# RFFI_pwrCtrl_Integrated_2021-05-07.net
KiCad netlist of a schematic drawn in EasyEDA
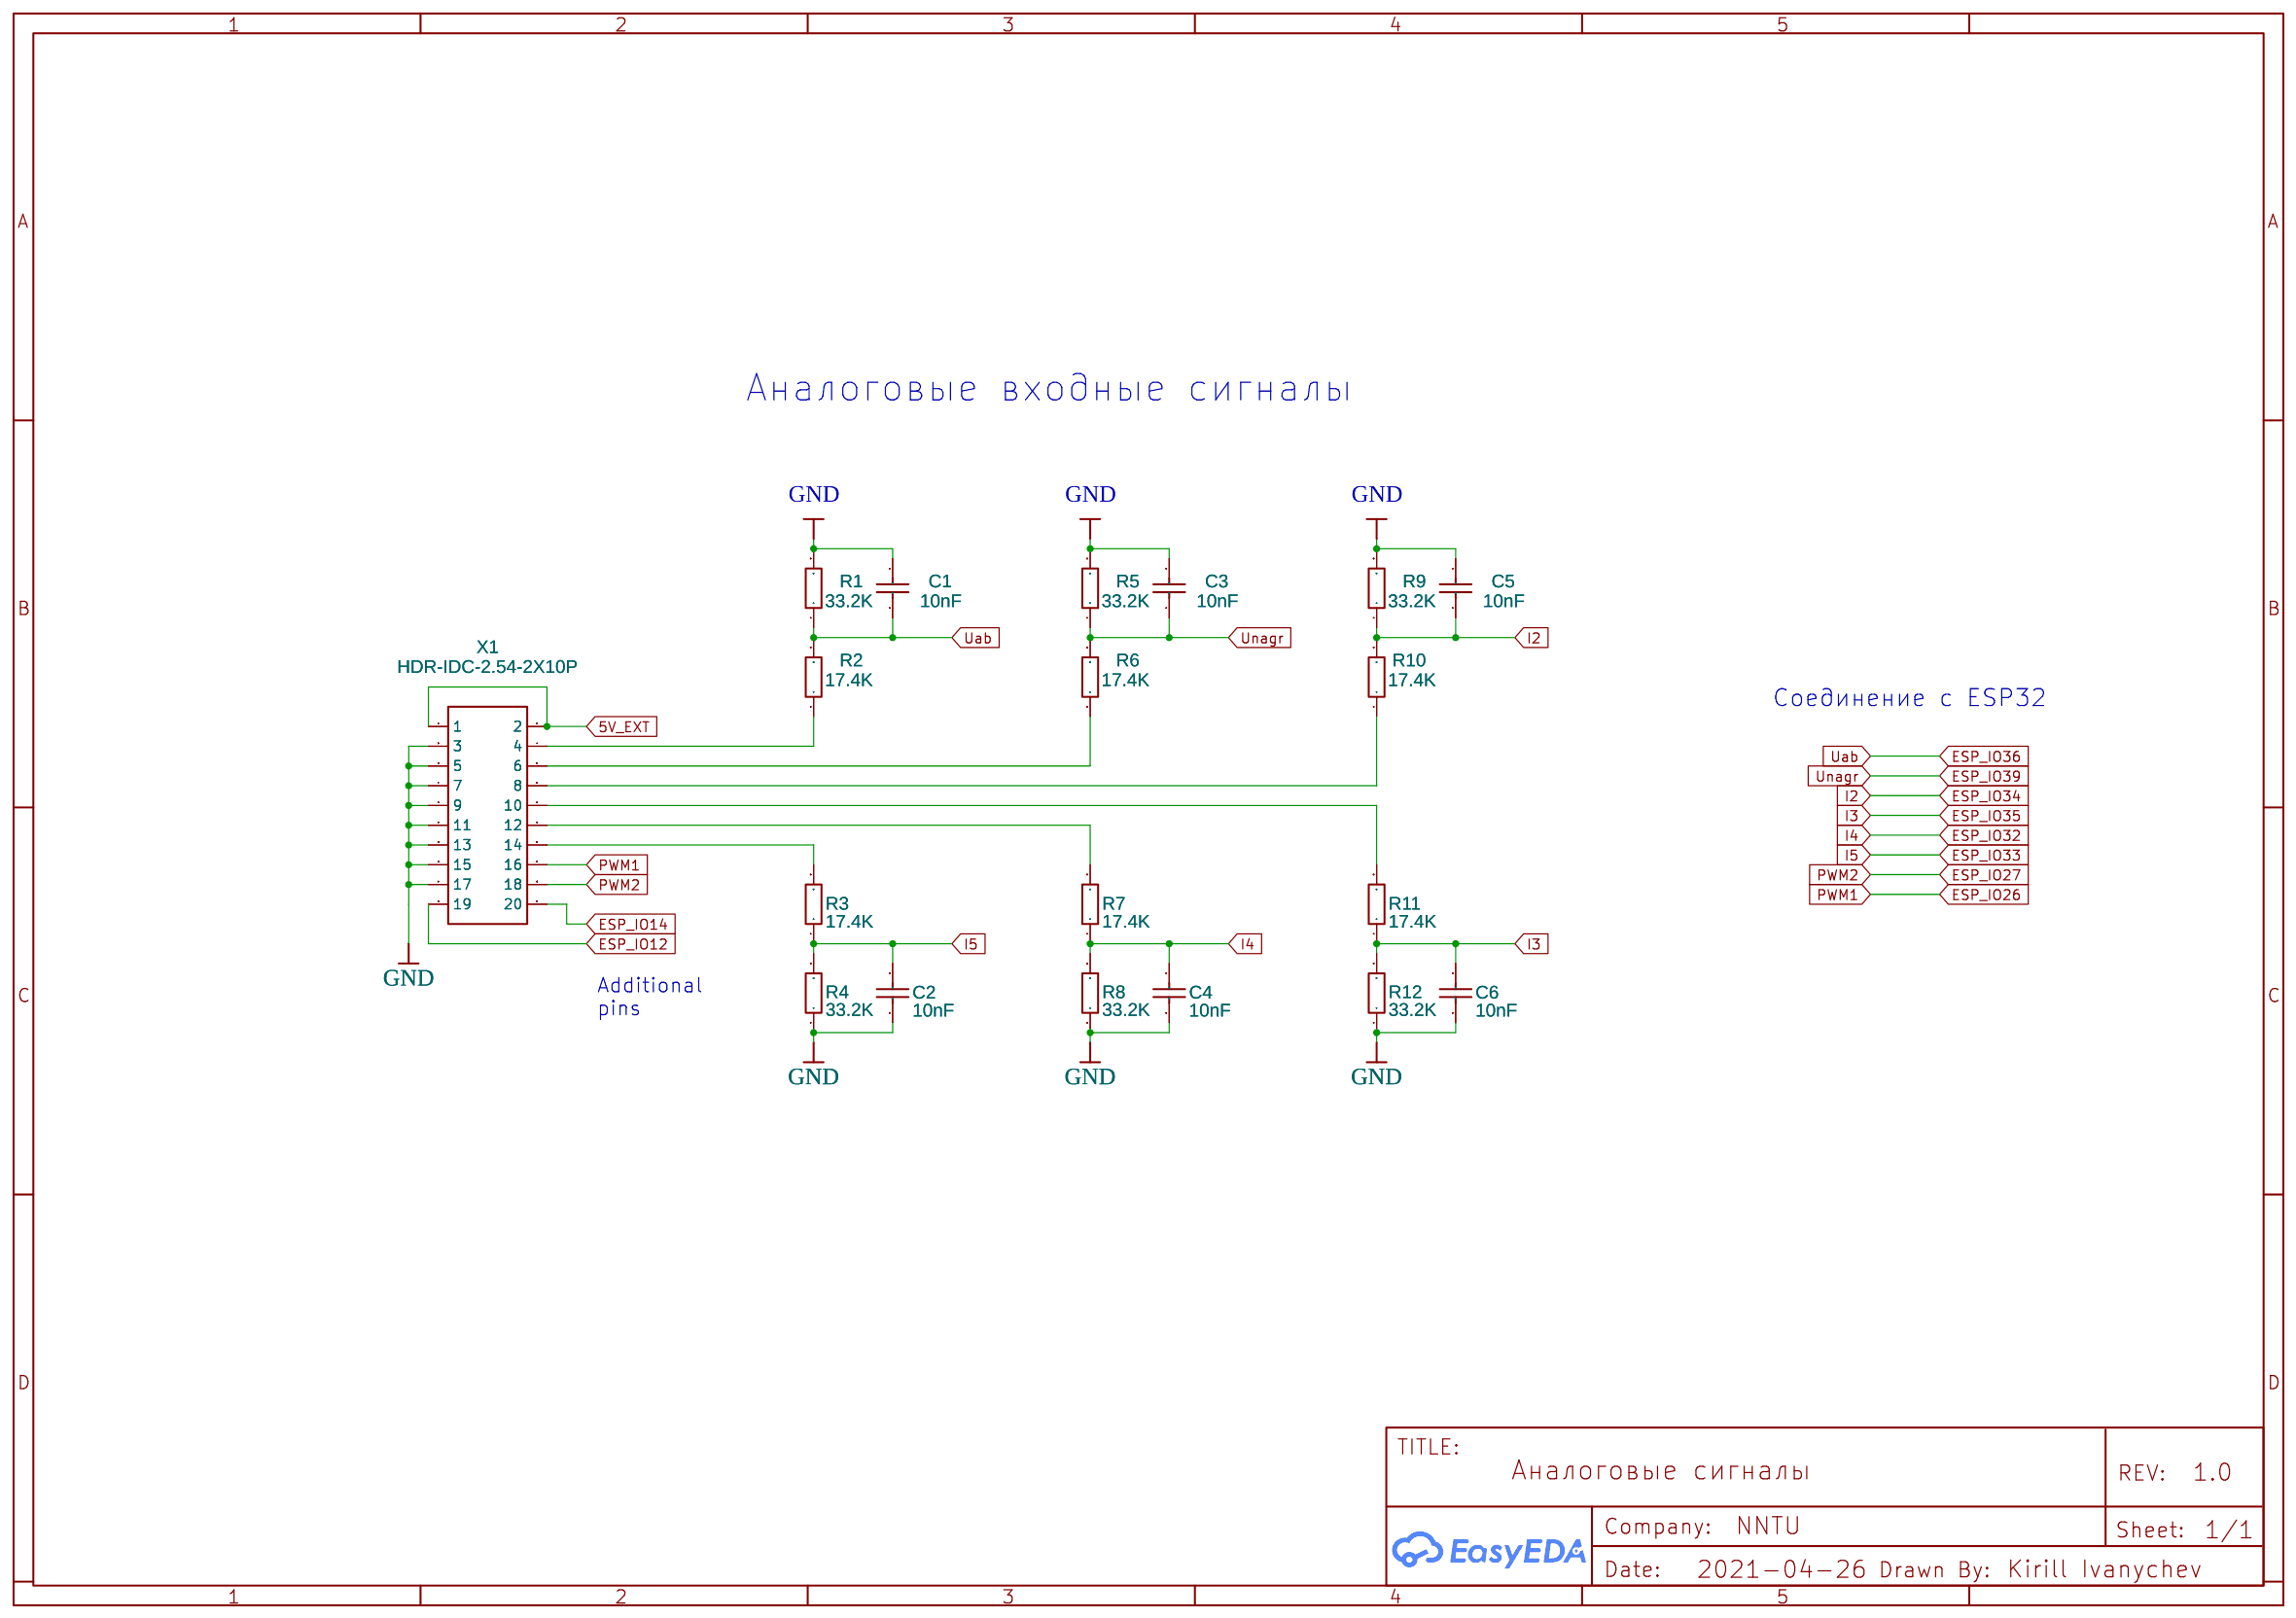
[diagram p0: Analog Signals]
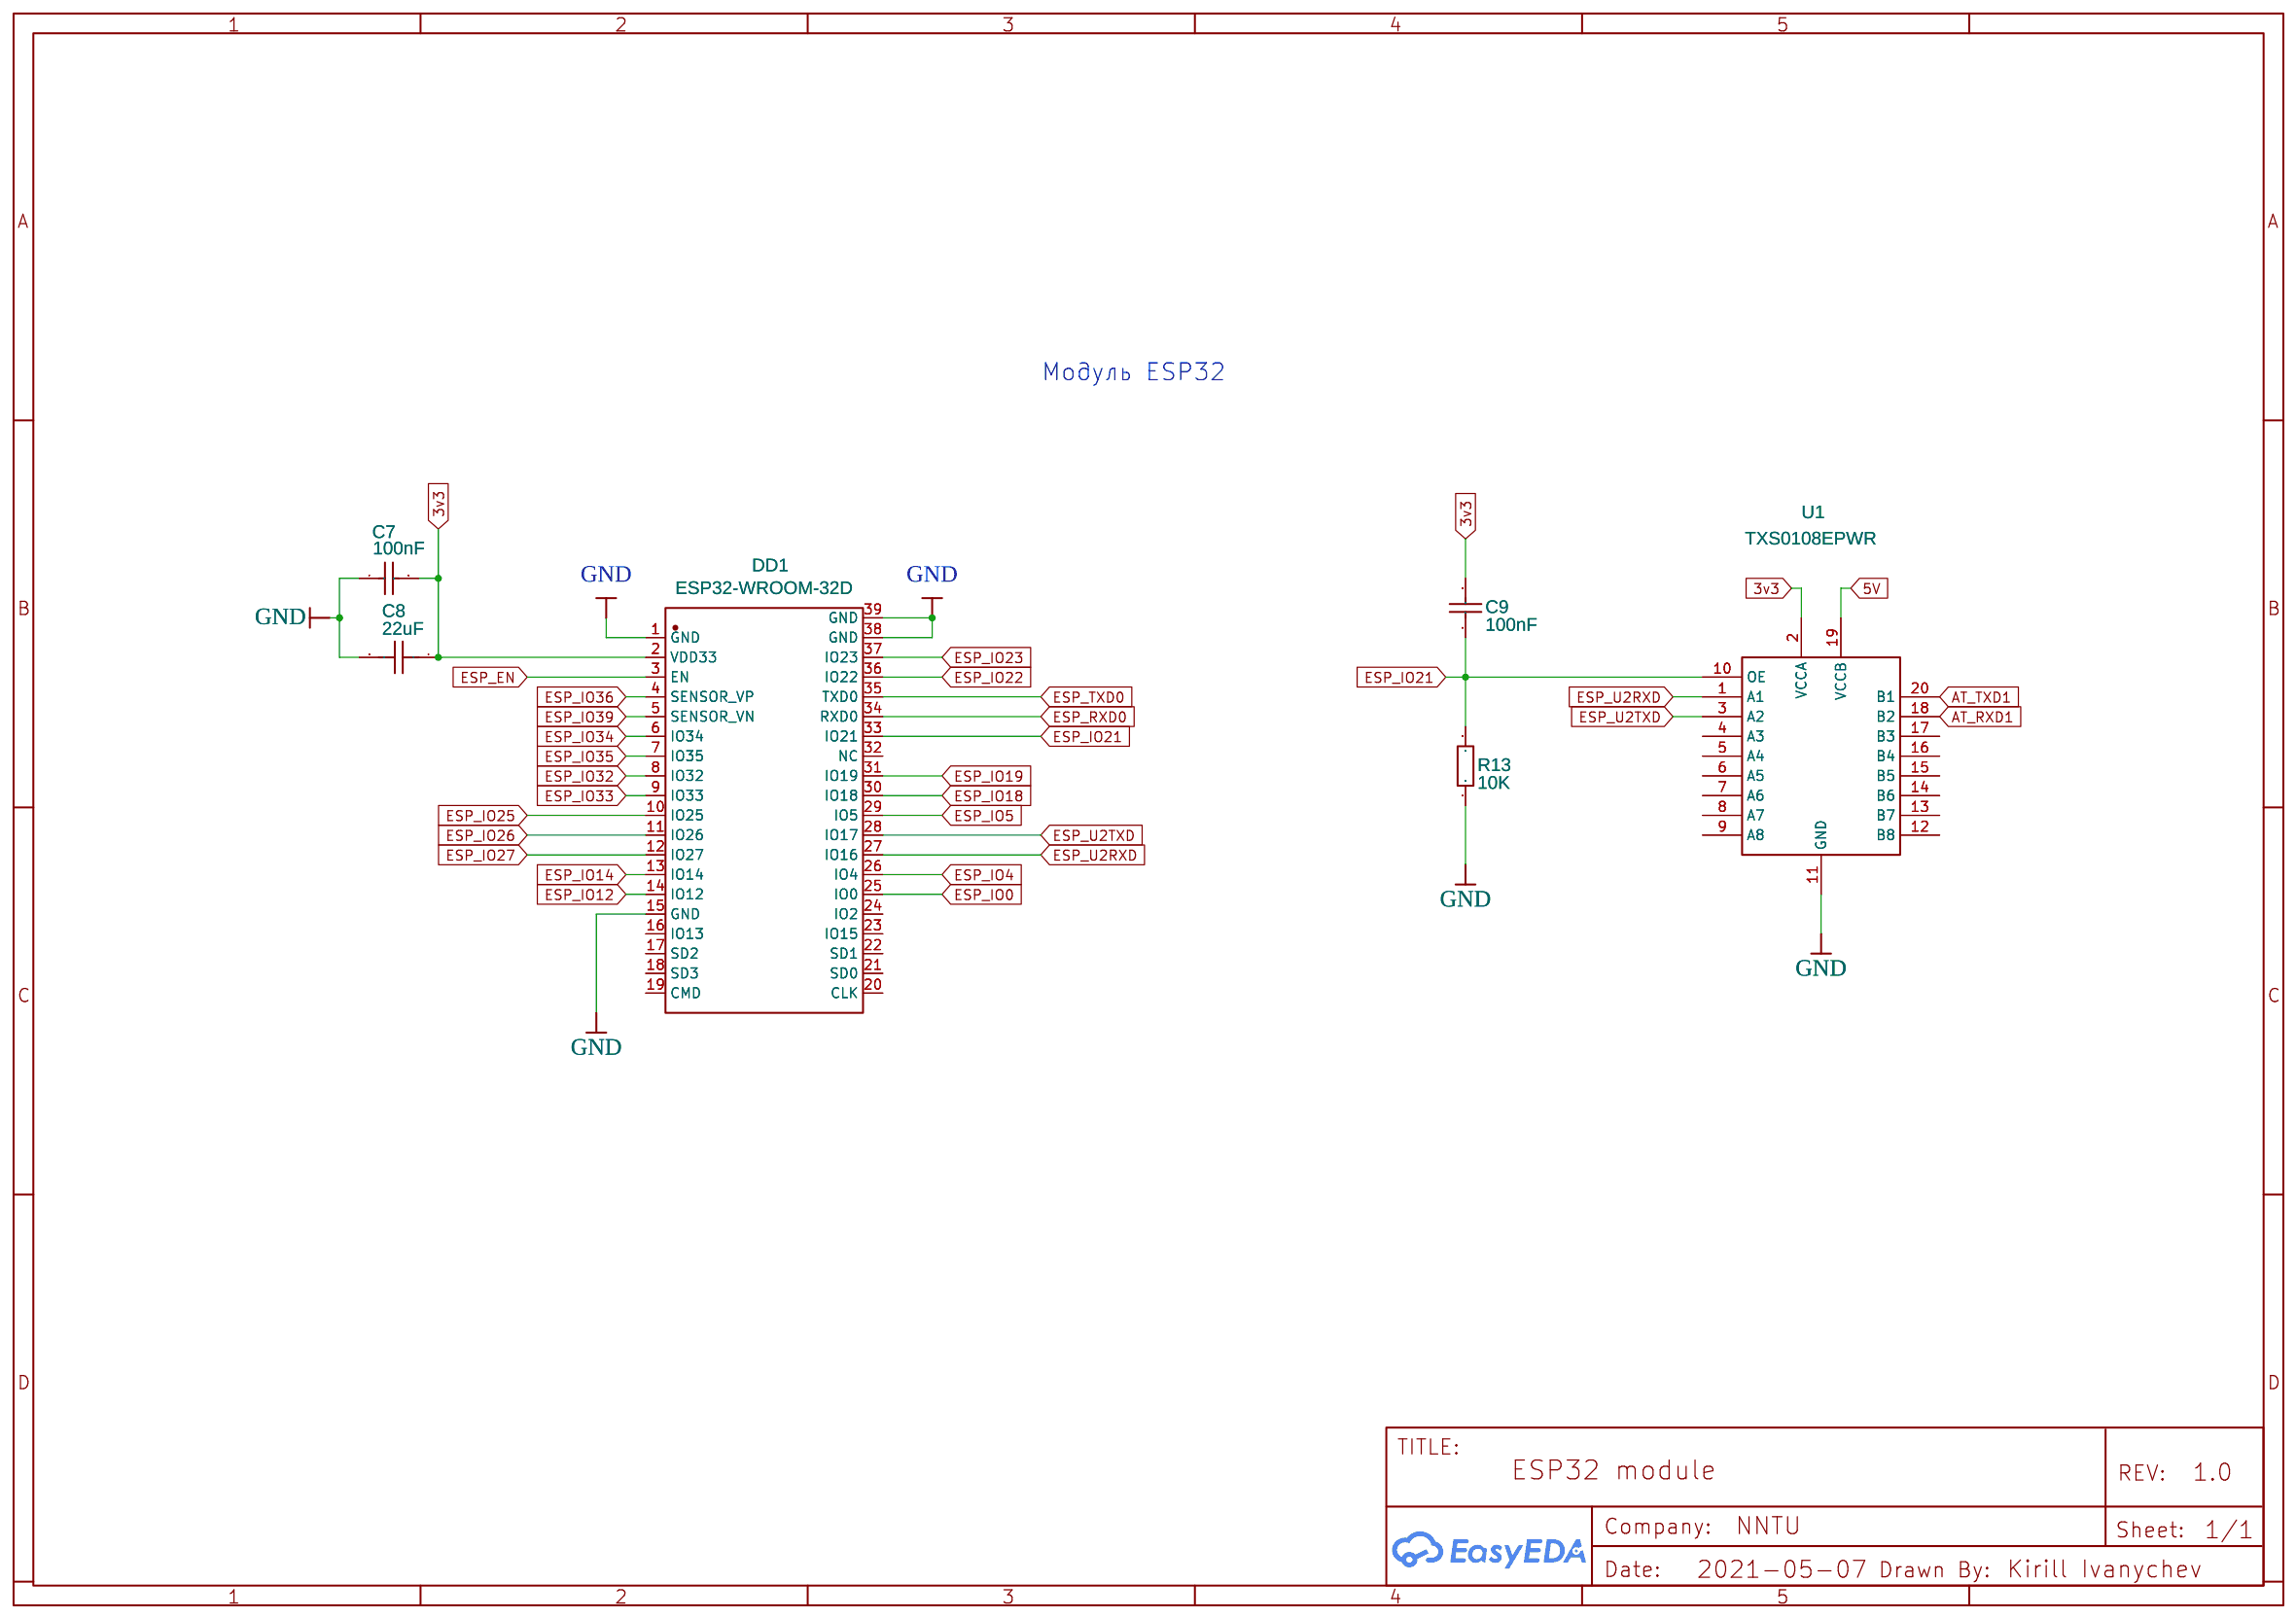
[diagram p1: ESP32 module]
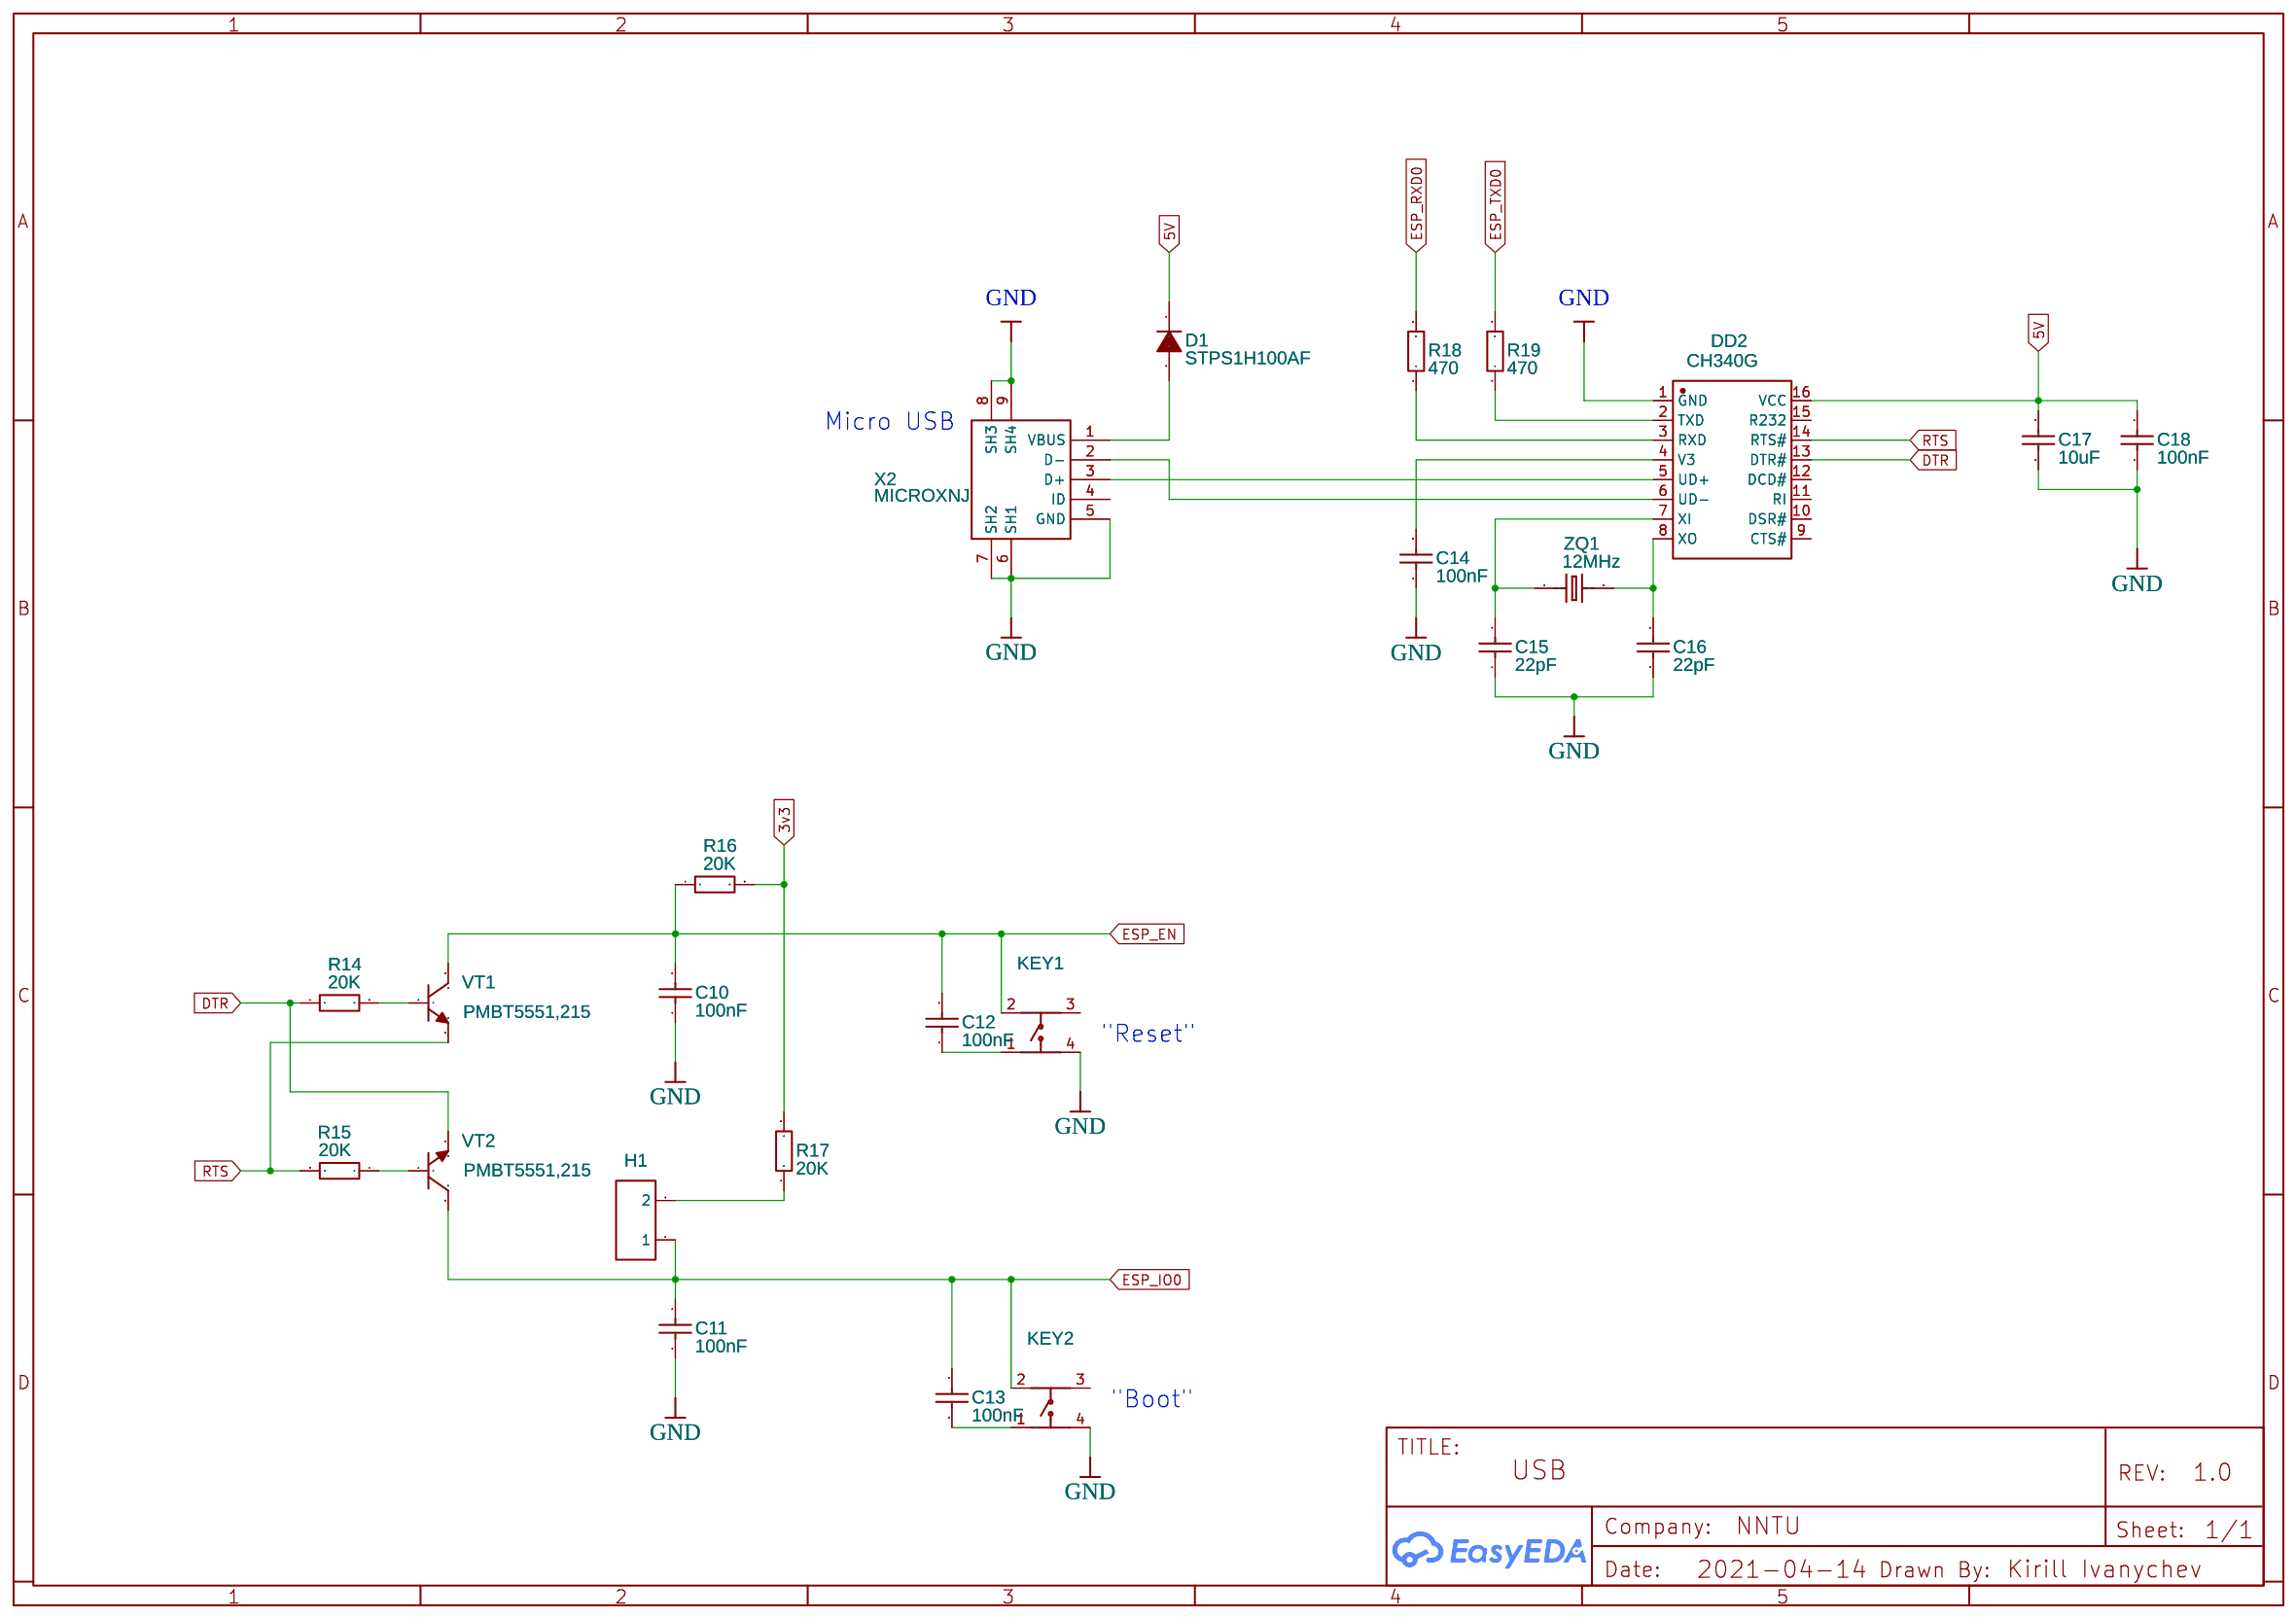
[diagram p2: USB]
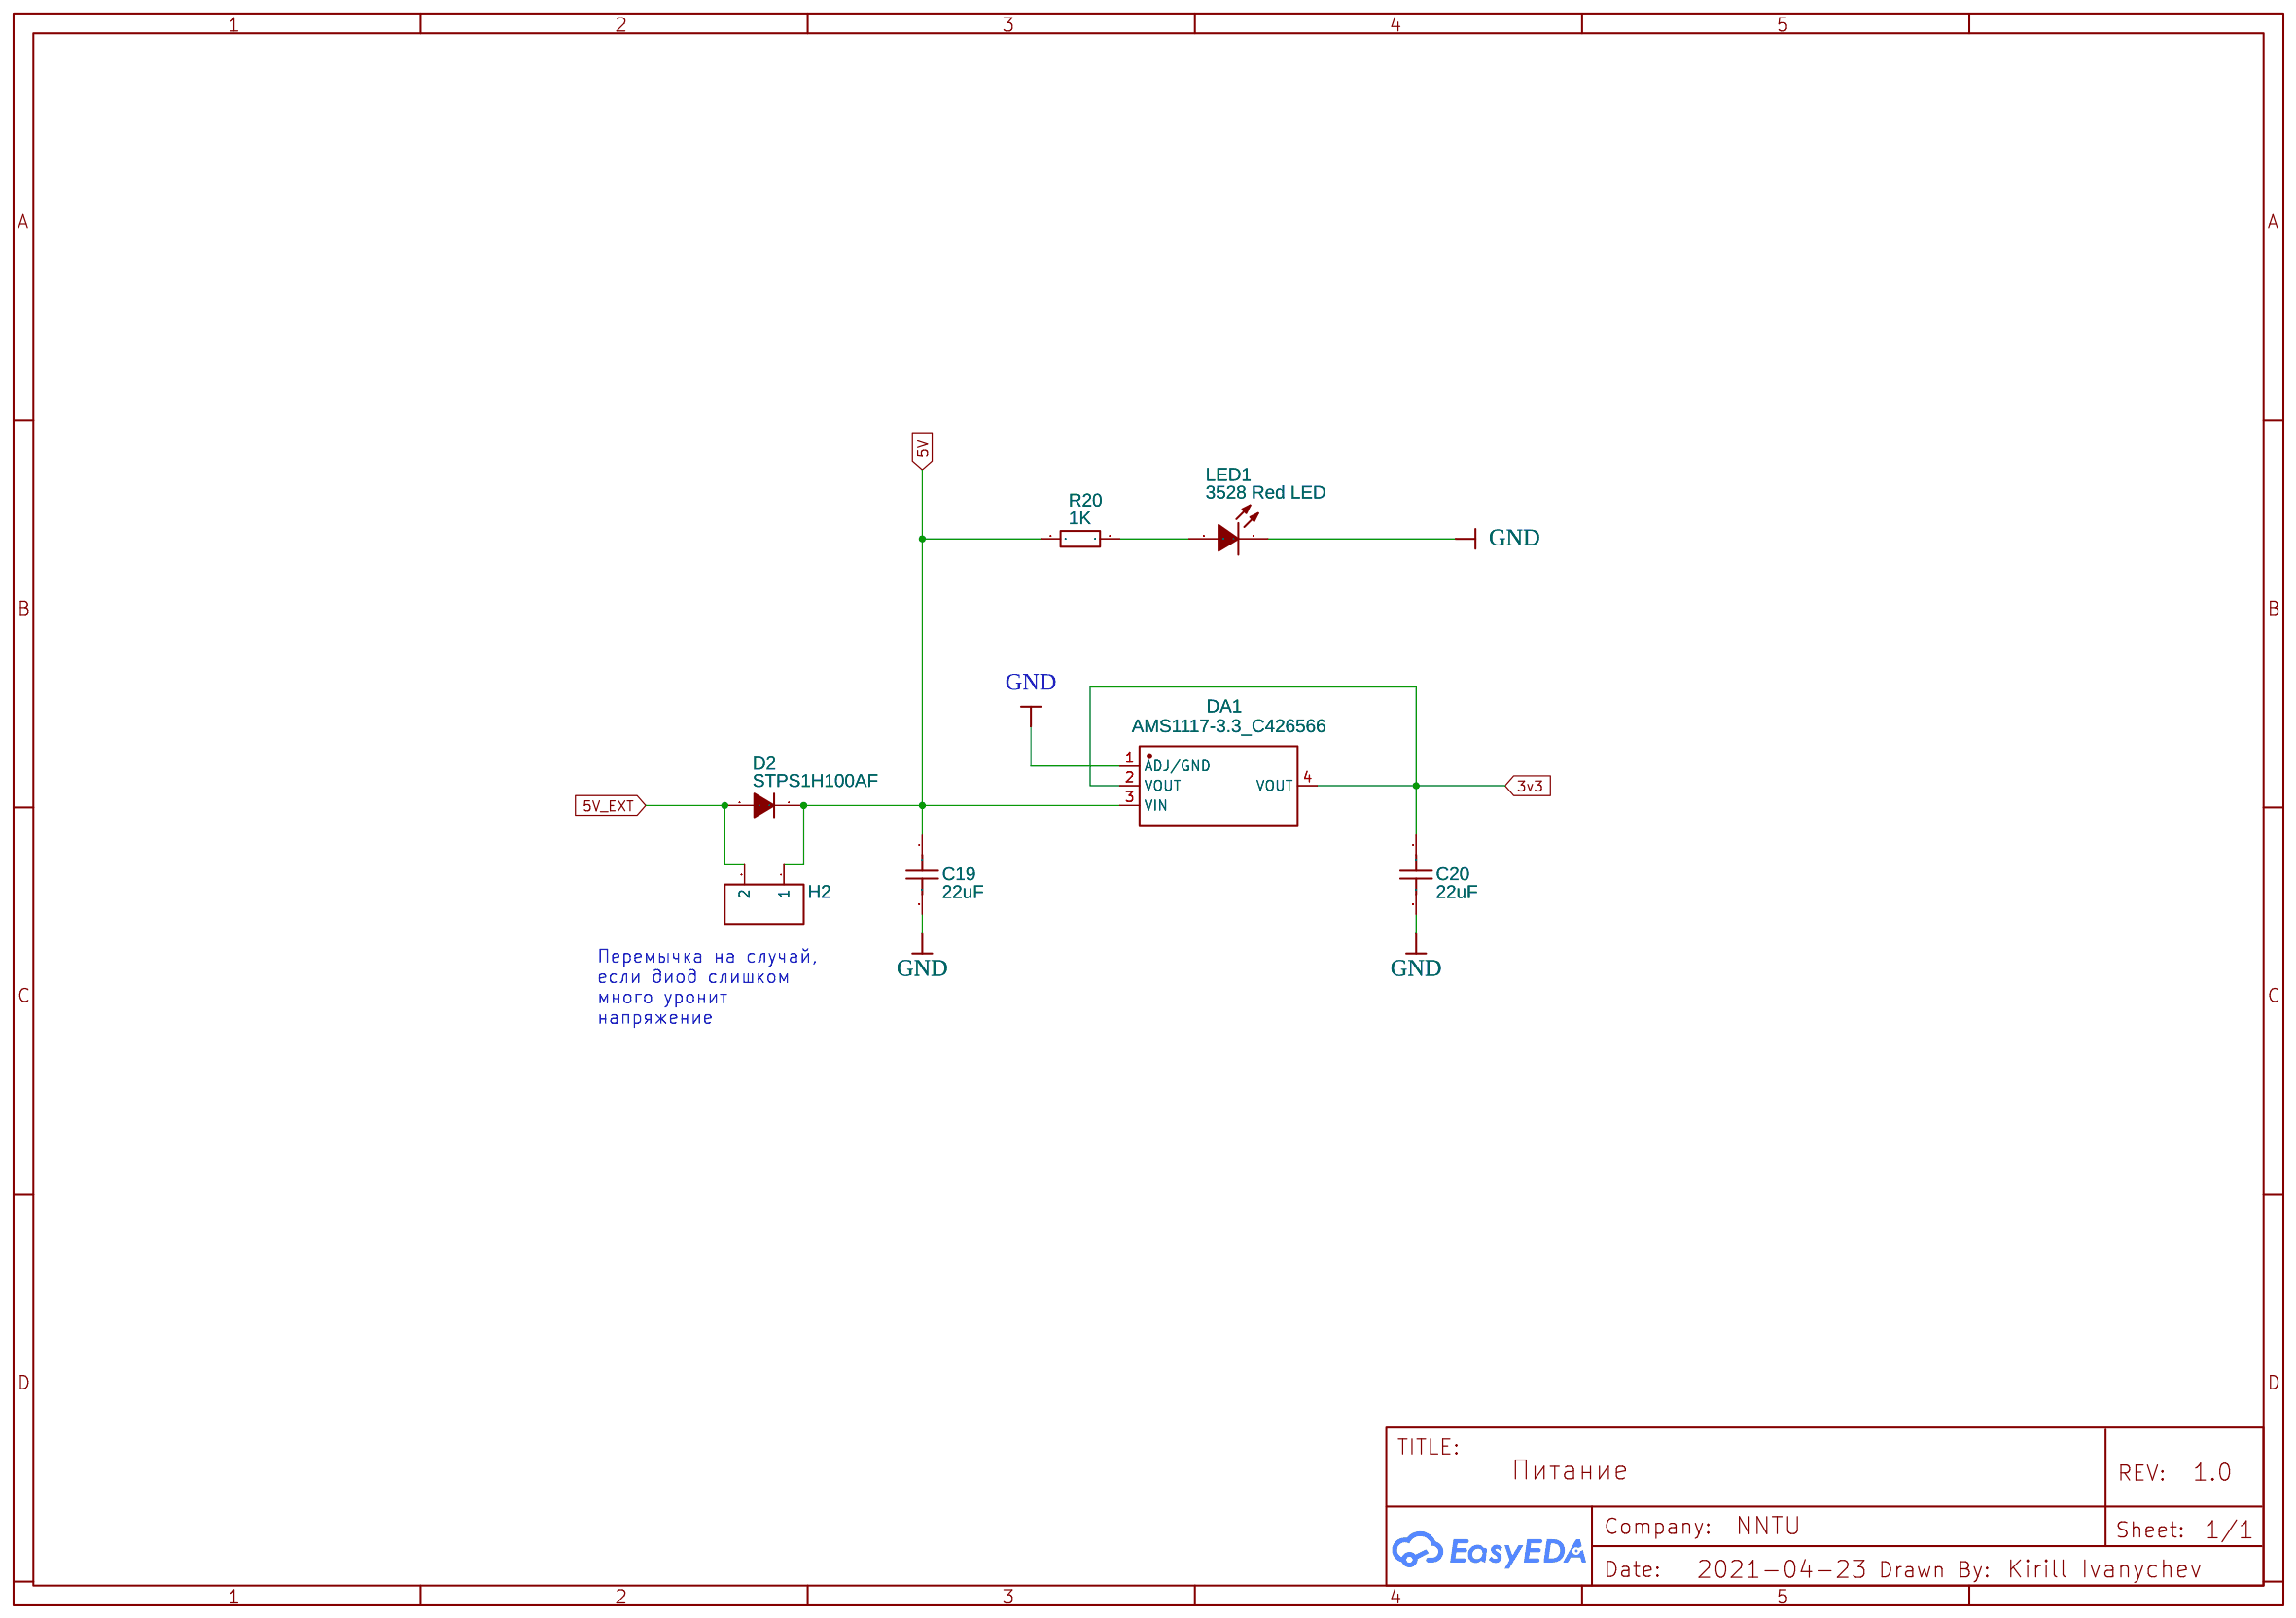
[diagram p3: Power]
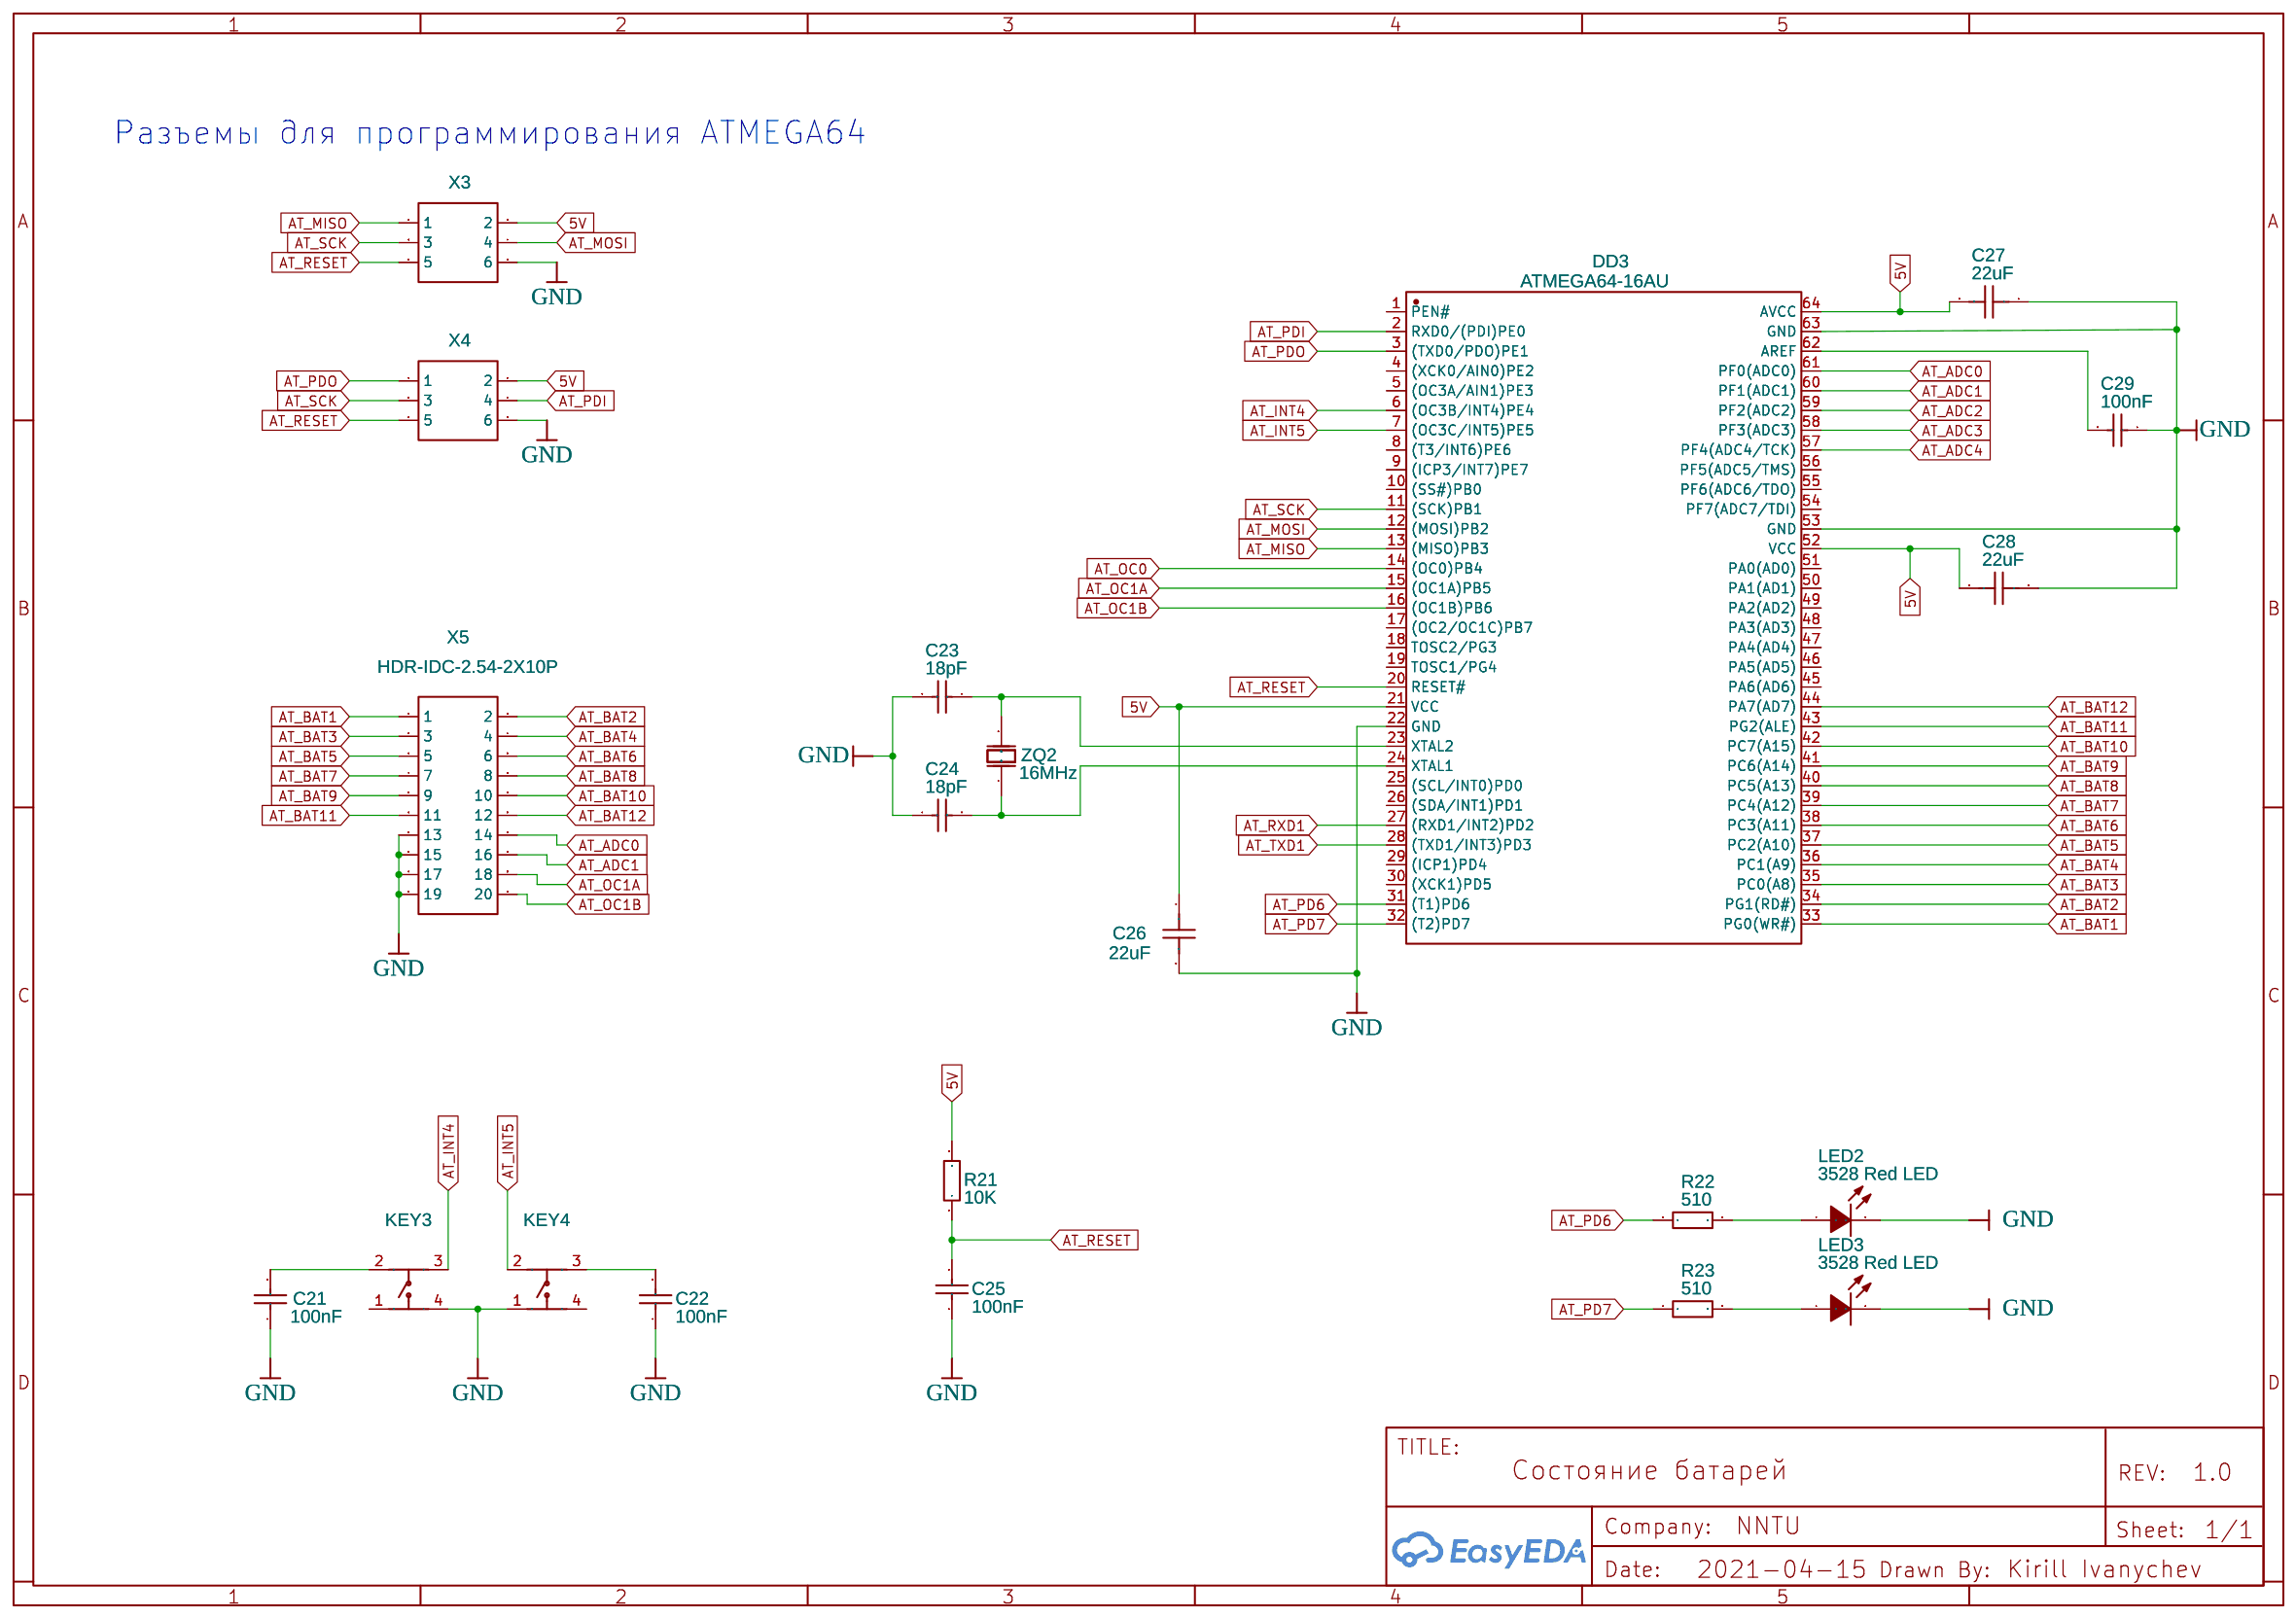
[diagram p4: Batteries]
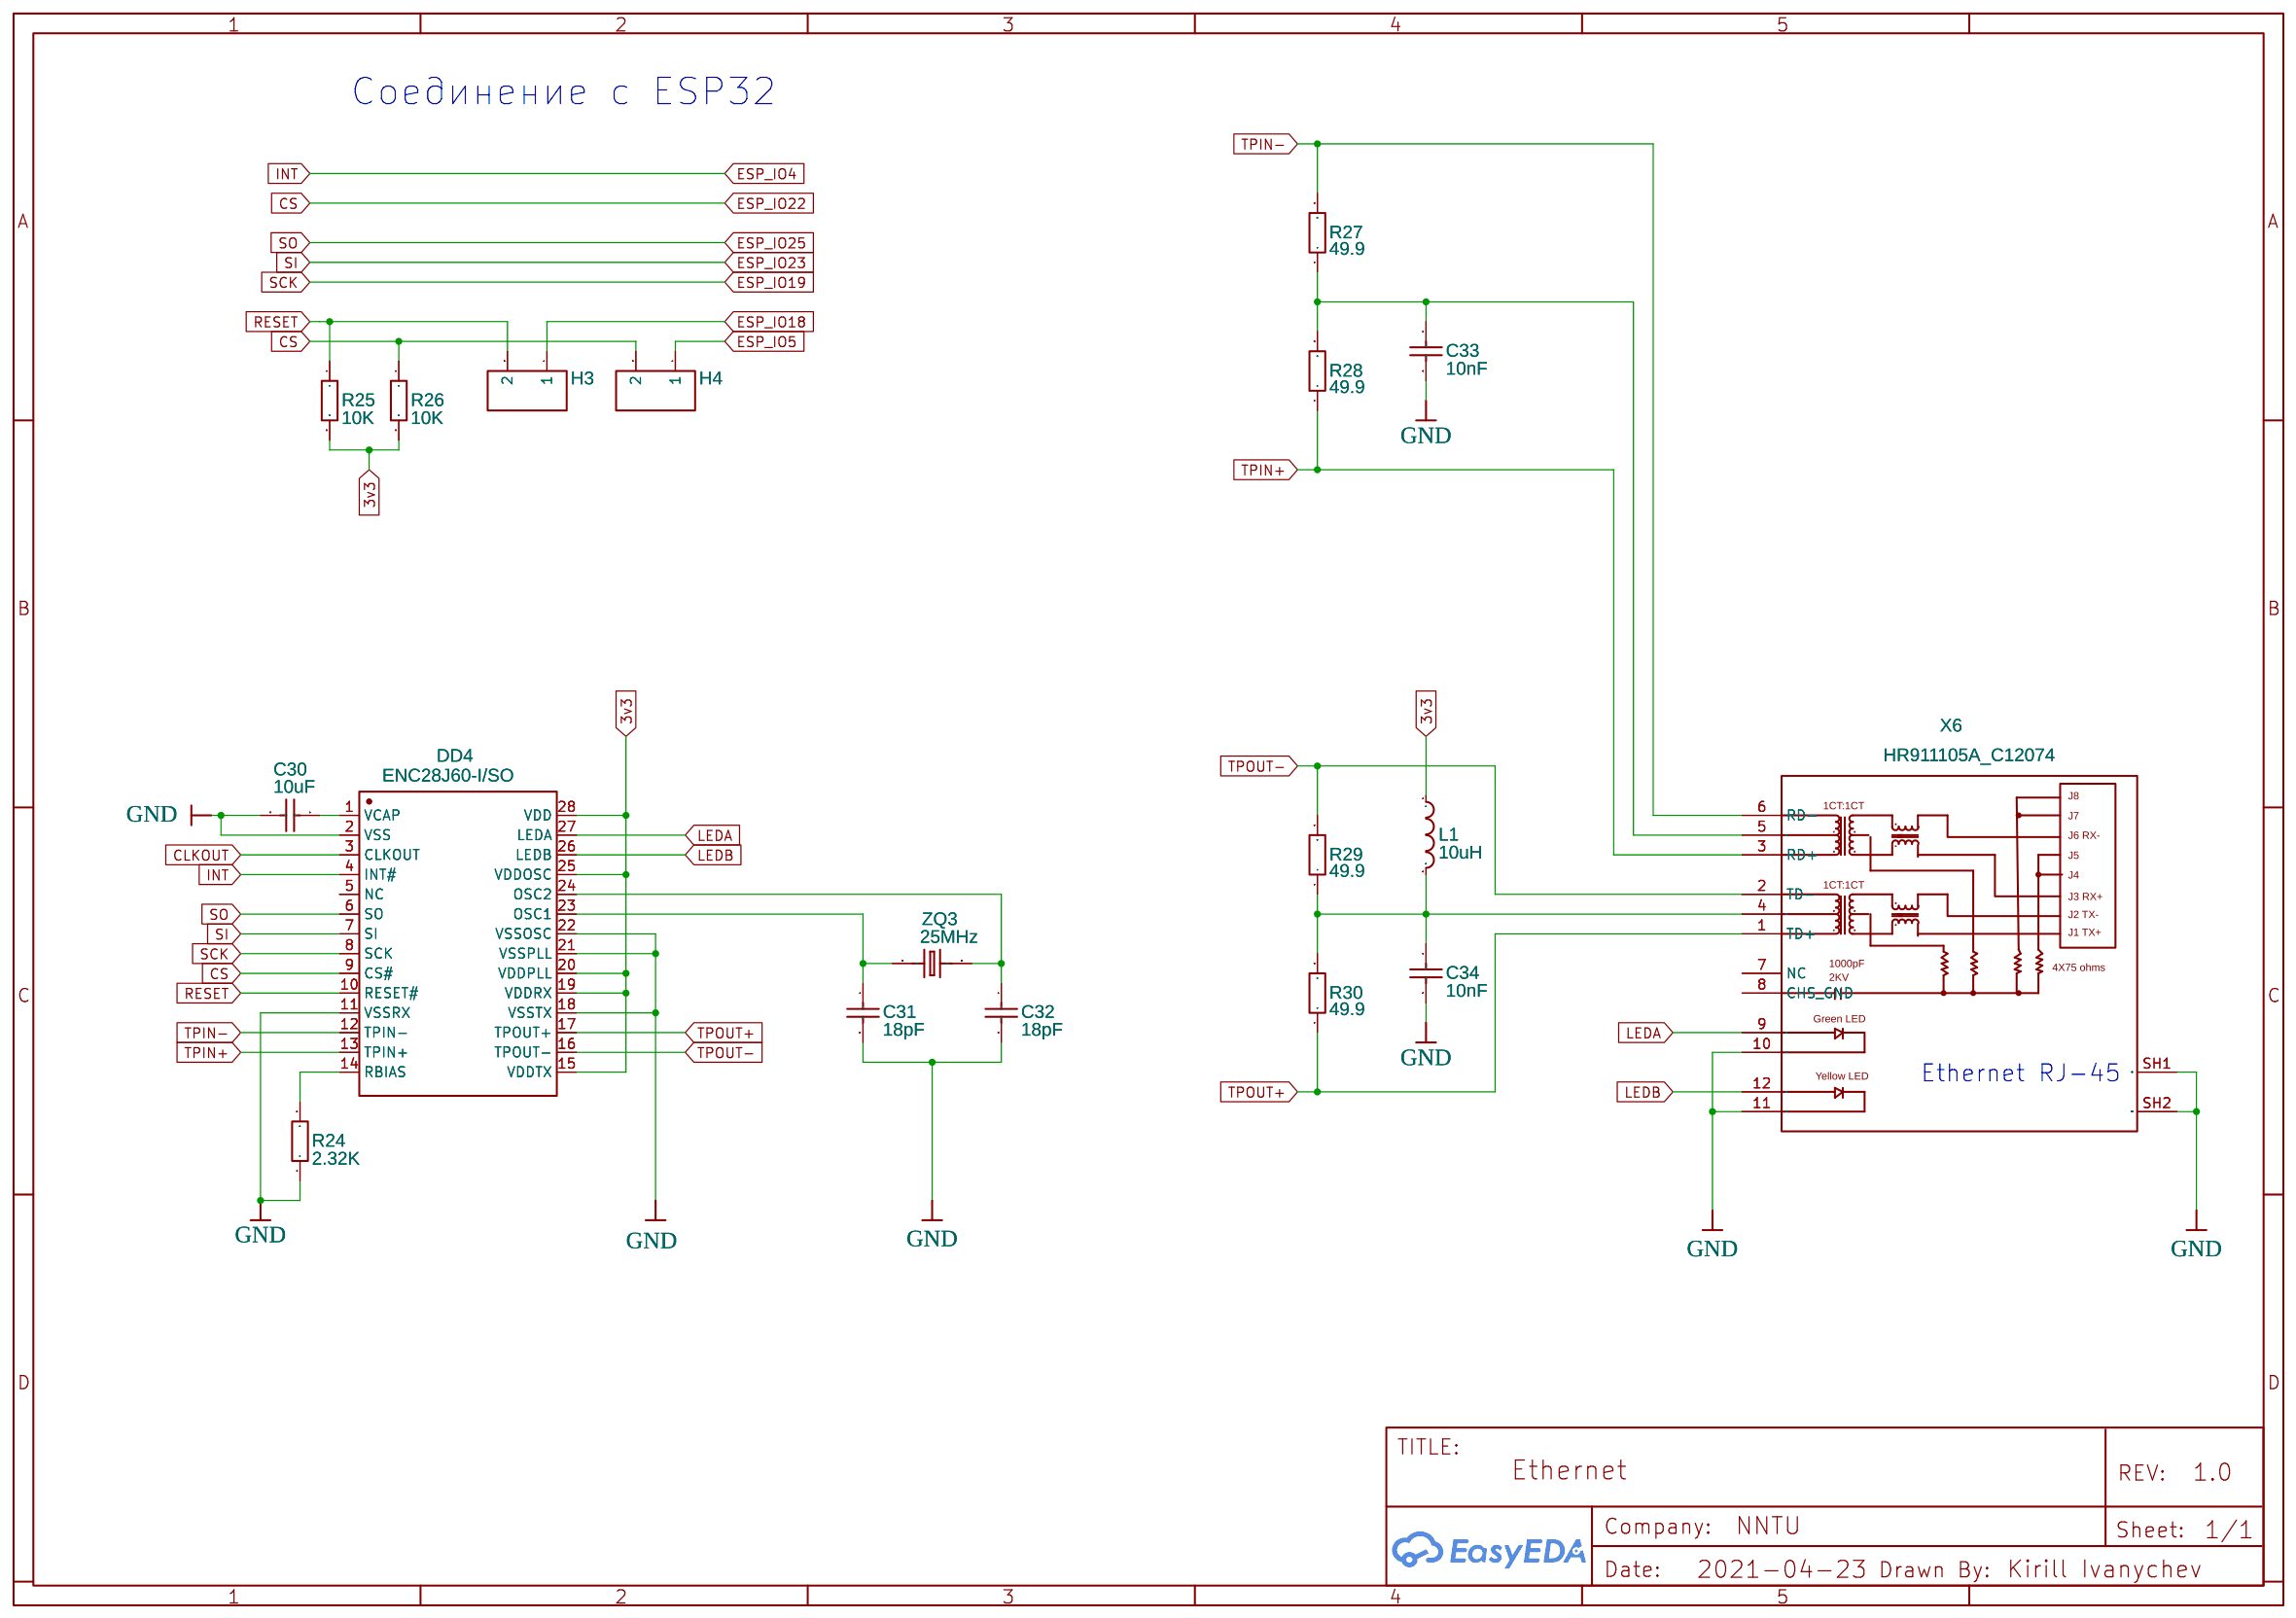
[diagram p5: Ethernet]

(export (version "E")
  (design (tool "Eeschema 10.0.6"))
  (components
    (comp (ref "C1")
      (value "10nF")
      (fields
        (field (name "BOM_Manufacturer Part") "1206B103K500NT")
        (field (name "BOM_Supplier Part") "C1846")
      )
      (libsource (lib "") (part "1206B103K500NT"))
    )
    (comp (ref "C2")
      (value "10nF")
      (fields
        (field (name "BOM_Manufacturer Part") "1206B103K500NT")
        (field (name "BOM_Supplier Part") "C1846")
      )
      (libsource (lib "") (part "1206B103K500NT_1"))
    )
    (comp (ref "C3")
      (value "10nF")
      (fields
        (field (name "BOM_Manufacturer Part") "1206B103K500NT")
        (field (name "BOM_Supplier Part") "C1846")
      )
      (libsource (lib "") (part "1206B103K500NT"))
    )
    (comp (ref "C4")
      (value "10nF")
      (fields
        (field (name "BOM_Manufacturer Part") "1206B103K500NT")
        (field (name "BOM_Supplier Part") "C1846")
      )
      (libsource (lib "") (part "1206B103K500NT_1"))
    )
    (comp (ref "C5")
      (value "10nF")
      (fields
        (field (name "BOM_Manufacturer Part") "1206B103K500NT")
        (field (name "BOM_Supplier Part") "C1846")
      )
      (libsource (lib "") (part "1206B103K500NT"))
    )
    (comp (ref "C6")
      (value "10nF")
      (fields
        (field (name "BOM_Manufacturer Part") "1206B103K500NT")
        (field (name "BOM_Supplier Part") "C1846")
      )
      (libsource (lib "") (part "1206B103K500NT_1"))
    )
    (comp (ref "R1")
      (value "33.2K")
      (fields
        (field (name "BOM_Manufacturer Part") "0603WAF3322T5E")
        (field (name "BOM_Supplier Part") "C23003")
      )
      (libsource (lib "") (part "0603WAF3322T5E"))
    )
    (comp (ref "R2")
      (value "17.4K")
      (fields
        (field (name "BOM_Manufacturer Part") "0402WGF1742TCE")
        (field (name "BOM_Supplier Part") "C26957")
      )
      (libsource (lib "") (part "0402WGF1742TCE"))
    )
    (comp (ref "R3")
      (value "17.4K")
      (fields
        (field (name "BOM_Manufacturer Part") "0402WGF1742TCE")
        (field (name "BOM_Supplier Part") "C26957")
      )
      (libsource (lib "") (part "0402WGF1742TCE"))
    )
    (comp (ref "R4")
      (value "33.2K")
      (fields
        (field (name "BOM_Manufacturer Part") "0603WAF3322T5E")
        (field (name "BOM_Supplier Part") "C23003")
      )
      (libsource (lib "") (part "0603WAF3322T5E"))
    )
    (comp (ref "R5")
      (value "33.2K")
      (fields
        (field (name "BOM_Manufacturer Part") "0603WAF3322T5E")
        (field (name "BOM_Supplier Part") "C23003")
      )
      (libsource (lib "") (part "0603WAF3322T5E"))
    )
    (comp (ref "R6")
      (value "17.4K")
      (fields
        (field (name "BOM_Manufacturer Part") "0402WGF1742TCE")
        (field (name "BOM_Supplier Part") "C26957")
      )
      (libsource (lib "") (part "0402WGF1742TCE"))
    )
    (comp (ref "R7")
      (value "17.4K")
      (fields
        (field (name "BOM_Manufacturer Part") "0402WGF1742TCE")
        (field (name "BOM_Supplier Part") "C26957")
      )
      (libsource (lib "") (part "0402WGF1742TCE"))
    )
    (comp (ref "R8")
      (value "33.2K")
      (fields
        (field (name "BOM_Manufacturer Part") "0603WAF3322T5E")
        (field (name "BOM_Supplier Part") "C23003")
      )
      (libsource (lib "") (part "0603WAF3322T5E"))
    )
    (comp (ref "R9")
      (value "33.2K")
      (fields
        (field (name "BOM_Manufacturer Part") "0603WAF3322T5E")
        (field (name "BOM_Supplier Part") "C23003")
      )
      (libsource (lib "") (part "0603WAF3322T5E"))
    )
    (comp (ref "R10")
      (value "17.4K")
      (fields
        (field (name "BOM_Manufacturer Part") "0402WGF1742TCE")
        (field (name "BOM_Supplier Part") "C26957")
      )
      (libsource (lib "") (part "0402WGF1742TCE"))
    )
    (comp (ref "R11")
      (value "17.4K")
      (fields
        (field (name "BOM_Manufacturer Part") "0402WGF1742TCE")
        (field (name "BOM_Supplier Part") "C26957")
      )
      (libsource (lib "") (part "0402WGF1742TCE"))
    )
    (comp (ref "R12")
      (value "33.2K")
      (fields
        (field (name "BOM_Manufacturer Part") "0603WAF3322T5E")
        (field (name "BOM_Supplier Part") "C23003")
      )
      (libsource (lib "") (part "0603WAF3322T5E"))
    )
    (comp (ref "X1")
      (value "HDR-IDC-2.54-2X10P")
      (fields
        (field (name "BOM_Manufacturer Part") "IDC Box 2.54mm 2X10P　Straight")
        (field (name "BOM_Supplier Part") "C3405")
      )
      (libsource (lib "") (part "HDR-IDC-2.54-2X10P"))
    )
    (comp (ref "C7")
      (value "100nF")
      (fields
        (field (name "BOM_Manufacturer Part") "CL21B104JBCNNNC")
        (field (name "BOM_Supplier Part") "C62912")
      )
      (libsource (lib "") (part "CL21B104JBCNNNC"))
    )
    (comp (ref "C8")
      (value "22uF")
      (fields
        (field (name "BOM_Manufacturer Part") "CL21A226MQQNNNE")
        (field (name "BOM_Supplier Part") "C5674")
      )
      (libsource (lib "") (part "CL21A226MQQNNNE"))
    )
    (comp (ref "C9")
      (value "100nF")
      (fields
        (field (name "BOM_Manufacturer Part") "CL21B104JBCNNNC")
        (field (name "BOM_Supplier Part") "C62912")
      )
      (libsource (lib "") (part "CL21B104JBCNNNC_1"))
    )
    (comp (ref "DD1")
      (value "ESP32-WROOM-32D")
      (fields (field (name "BOM_Supplier Part") "C473012"))
      (libsource (lib "") (part "ESP32-WROOM-32D"))
    )
    (comp (ref "R13")
      (value "10K")
      (fields
        (field (name "BOM_Manufacturer Part") "ARG03FTC1002")
        (field (name "BOM_Supplier Part") "C217687")
      )
      (libsource (lib "") (part "ARG03FTC1002"))
    )
    (comp (ref "U1")
      (value "TXS0108EPWR")
      (fields (field (name "BOM_Supplier Part") "C17206"))
      (libsource (lib "") (part "TXS0108EPWR"))
    )
    (comp (ref "C10")
      (value "100nF")
      (fields
        (field (name "BOM_Manufacturer Part") "CL21B104JBCNNNC")
        (field (name "BOM_Supplier Part") "C62912")
      )
      (libsource (lib "") (part "CL21B104JBCNNNC"))
    )
    (comp (ref "C11")
      (value "100nF")
      (fields
        (field (name "BOM_Manufacturer Part") "CL21B104JBCNNNC")
        (field (name "BOM_Supplier Part") "C62912")
      )
      (libsource (lib "") (part "CL21B104JBCNNNC"))
    )
    (comp (ref "C12")
      (value "100nF")
      (fields
        (field (name "BOM_Manufacturer Part") "CL21B104JBCNNNC")
        (field (name "BOM_Supplier Part") "C62912")
      )
      (libsource (lib "") (part "CL21B104JBCNNNC"))
    )
    (comp (ref "C13")
      (value "100nF")
      (fields
        (field (name "BOM_Manufacturer Part") "CL21B104JBCNNNC")
        (field (name "BOM_Supplier Part") "C62912")
      )
      (libsource (lib "") (part "CL21B104JBCNNNC"))
    )
    (comp (ref "C14")
      (value "100nF")
      (fields
        (field (name "BOM_Manufacturer Part") "CL21B104JBCNNNC")
        (field (name "BOM_Supplier Part") "C62912")
      )
      (libsource (lib "") (part "CL21B104JBCNNNC"))
    )
    (comp (ref "C15")
      (value "22pF")
      (fields
        (field (name "BOM_Manufacturer Part") "CL10C220JB8NNNC")
        (field (name "BOM_Supplier Part") "C1653")
      )
      (libsource (lib "") (part "CL10C220JB8NNNC"))
    )
    (comp (ref "C16")
      (value "22pF")
      (fields
        (field (name "BOM_Manufacturer Part") "CL10C220JB8NNNC")
        (field (name "BOM_Supplier Part") "C1653")
      )
      (libsource (lib "") (part "CL10C220JB8NNNC"))
    )
    (comp (ref "C17")
      (value "10uF")
      (fields
        (field (name "BOM_Manufacturer Part") "CL31B106KOHNNNE")
        (field (name "BOM_Supplier Part") "C47971")
      )
      (libsource (lib "") (part "CL31B106KOHNNNE"))
    )
    (comp (ref "C18")
      (value "100nF")
      (fields
        (field (name "BOM_Manufacturer Part") "CL21B104JBCNNNC")
        (field (name "BOM_Supplier Part") "C62912")
      )
      (libsource (lib "") (part "CL21B104JBCNNNC"))
    )
    (comp (ref "D1")
      (value "STPS1H100AF")
      (fields (field (name "BOM_Supplier Part") "C361044"))
      (libsource (lib "") (part "STPS1H100AF"))
    )
    (comp (ref "DD2")
      (value "CH340G")
      (fields (field (name "BOM_Supplier Part") "C14267"))
      (libsource (lib "") (part "CH340G"))
    )
    (comp (ref "H1")
      (value "Header-Male-2.54_1x2")
      (fields (field (name "BOM_Manufacturer Part") "826629-2") (field (name "BOM_Supplier Part") "C86471"))
      (libsource (lib "") (part "Header-Male-2.54_1x2"))
    )
    (comp (ref "KEY1")
      (value "TSA063G50-250")
      (fields (field (name "BOM_Supplier Part") "C294565"))
      (libsource (lib "") (part "TSA063G50-250"))
    )
    (comp (ref "KEY2")
      (value "TSA063G50-250")
      (fields (field (name "BOM_Supplier Part") "C294565"))
      (libsource (lib "") (part "TSA063G50-250"))
    )
    (comp (ref "R14")
      (value "20K")
      (fields
        (field (name "BOM_Manufacturer Part") "0805W8F2002T5E")
        (field (name "BOM_Supplier Part") "C4328")
      )
      (libsource (lib "") (part "0805W8F2002T5E_1"))
    )
    (comp (ref "R15")
      (value "20K")
      (fields
        (field (name "BOM_Manufacturer Part") "0805W8F2002T5E")
        (field (name "BOM_Supplier Part") "C4328")
      )
      (libsource (lib "") (part "0805W8F2002T5E"))
    )
    (comp (ref "R16")
      (value "20K")
      (fields
        (field (name "BOM_Manufacturer Part") "0805W8F2002T5E")
        (field (name "BOM_Supplier Part") "C4328")
      )
      (libsource (lib "") (part "0805W8F2002T5E_1"))
    )
    (comp (ref "R17")
      (value "20K")
      (fields
        (field (name "BOM_Manufacturer Part") "0805W8F2002T5E")
        (field (name "BOM_Supplier Part") "C4328")
      )
      (libsource (lib "") (part "0805W8F2002T5E_2"))
    )
    (comp (ref "R18")
      (value "470")
      (fields
        (field (name "BOM_Manufacturer Part") "1206W4J0471T5E")
        (field (name "BOM_Supplier Part") "C25383")
      )
      (libsource (lib "") (part "1206W4J0471T5E"))
    )
    (comp (ref "R19")
      (value "470")
      (fields
        (field (name "BOM_Manufacturer Part") "1206W4J0471T5E")
        (field (name "BOM_Supplier Part") "C25383")
      )
      (libsource (lib "") (part "1206W4J0471T5E"))
    )
    (comp (ref "VT1")
      (value "PMBT5551,215")
      (fields (field (name "BOM_Supplier Part") "C75557"))
      (libsource (lib "") (part "PMBT5551,215_1"))
    )
    (comp (ref "VT2")
      (value "PMBT5551,215")
      (fields (field (name "BOM_Supplier Part") "C75557"))
      (libsource (lib "") (part "PMBT5551,215"))
    )
    (comp (ref "X2")
      (value "MICROXNJ")
      (fields (field (name "BOM_Manufacturer Part") "MicroXNJ") (field (name "BOM_Supplier Part") "C404969"))
      (libsource (lib "") (part "MICROXNJ"))
    )
    (comp (ref "ZQ1")
      (value "12MHz")
      (fields
        (field (name "BOM_Manufacturer Part") "HC-49S12MHz20pF30PPM")
        (field (name "BOM_Supplier Part") "C127674")
      )
      (libsource (lib "") (part "HC-49S12MHZ20PF30PPM"))
    )
    (comp (ref "C19")
      (value "22uF")
      (fields
        (field (name "BOM_Manufacturer Part") "CL21A226MQQNNNE")
        (field (name "BOM_Supplier Part") "C5674")
      )
      (libsource (lib "") (part "CL21A226MQQNNNE"))
    )
    (comp (ref "C20")
      (value "22uF")
      (fields
        (field (name "BOM_Manufacturer Part") "CL21A226MQQNNNE")
        (field (name "BOM_Supplier Part") "C5674")
      )
      (libsource (lib "") (part "CL21A226MQQNNNE"))
    )
    (comp (ref "D2")
      (value "STPS1H100AF")
      (fields (field (name "BOM_Supplier Part") "C361044"))
      (libsource (lib "") (part "STPS1H100AF"))
    )
    (comp (ref "DA1")
      (value "AMS1117-3.3_C426566")
      (fields
        (field (name "BOM_Manufacturer Part") "AMS1117-3.3")
        (field (name "BOM_Supplier Part") "C426566")
      )
      (libsource (lib "") (part "AMS1117-3.3_C426566"))
    )
    (comp (ref "H2")
      (value "Header-Male-2.54_1x2")
      (fields (field (name "BOM_Manufacturer Part") "826629-2") (field (name "BOM_Supplier Part") "C86471"))
      (libsource (lib "") (part "Header-Male-2.54_1x2"))
    )
    (comp (ref "LED1")
      (value "3528 Red LED")
      (fields (field (name "BOM_Supplier Part") "C2305"))
      (libsource (lib "") (part "3528 Red LED"))
    )
    (comp (ref "R20")
      (value "1K")
      (fields
        (field (name "BOM_Manufacturer Part") "TC0525F1001T5E")
        (field (name "BOM_Supplier Part") "C75781")
      )
      (libsource (lib "") (part "TC0525F1001T5E"))
    )
    (comp (ref "C21")
      (value "100nF")
      (fields
        (field (name "BOM_Manufacturer Part") "CL21B104JBCNNNC")
        (field (name "BOM_Supplier Part") "C62912")
      )
      (libsource (lib "") (part "CL21B104JBCNNNC"))
    )
    (comp (ref "C22")
      (value "100nF")
      (fields
        (field (name "BOM_Manufacturer Part") "CL21B104JBCNNNC")
        (field (name "BOM_Supplier Part") "C62912")
      )
      (libsource (lib "") (part "CL21B104JBCNNNC"))
    )
    (comp (ref "C23")
      (value "18pF")
      (fields
        (field (name "BOM_Manufacturer Part") "0402CG180J500NT")
        (field (name "BOM_Supplier Part") "C1549")
      )
      (libsource (lib "") (part "0402CG180J500NT_1"))
    )
    (comp (ref "C24")
      (value "18pF")
      (fields
        (field (name "BOM_Manufacturer Part") "0402CG180J500NT")
        (field (name "BOM_Supplier Part") "C1549")
      )
      (libsource (lib "") (part "0402CG180J500NT"))
    )
    (comp (ref "C25")
      (value "100nF")
      (fields
        (field (name "BOM_Manufacturer Part") "CL21B104JBCNNNC")
        (field (name "BOM_Supplier Part") "C62912")
      )
      (libsource (lib "") (part "CL21B104JBCNNNC"))
    )
    (comp (ref "C26")
      (value "22uF")
      (fields
        (field (name "BOM_Manufacturer Part") "CL21A226MQQNNNE")
        (field (name "BOM_Supplier Part") "C5674")
      )
      (libsource (lib "") (part "CL21A226MQQNNNE"))
    )
    (comp (ref "C27")
      (value "22uF")
      (fields
        (field (name "BOM_Manufacturer Part") "CL21A226MQQNNNE")
        (field (name "BOM_Supplier Part") "C5674")
      )
      (libsource (lib "") (part "CL21A226MQQNNNE_2"))
    )
    (comp (ref "C28")
      (value "22uF")
      (fields
        (field (name "BOM_Manufacturer Part") "CL21A226MQQNNNE")
        (field (name "BOM_Supplier Part") "C5674")
      )
      (libsource (lib "") (part "CL21A226MQQNNNE_1"))
    )
    (comp (ref "C29")
      (value "100nF")
      (fields
        (field (name "BOM_Manufacturer Part") "CL21B104JBCNNNC")
        (field (name "BOM_Supplier Part") "C62912")
      )
      (libsource (lib "") (part "CL21B104JBCNNNC_1"))
    )
    (comp (ref "DD3")
      (value "ATMEGA64-16AU")
      (fields (field (name "BOM_Supplier Part") "C219170"))
      (libsource (lib "") (part "ATMEGA64-16AU"))
    )
    (comp (ref "KEY3")
      (value "TSA063G50-250")
      (fields (field (name "BOM_Supplier Part") "C294565"))
      (libsource (lib "") (part "TSA063G50-250"))
    )
    (comp (ref "KEY4")
      (value "TSA063G50-250")
      (fields (field (name "BOM_Supplier Part") "C294565"))
      (libsource (lib "") (part "TSA063G50-250"))
    )
    (comp (ref "LED2")
      (value "3528 Red LED")
      (fields (field (name "BOM_Supplier Part") "C2305"))
      (libsource (lib "") (part "3528 Red LED"))
    )
    (comp (ref "LED3")
      (value "3528 Red LED")
      (fields (field (name "BOM_Supplier Part") "C2305"))
      (libsource (lib "") (part "3528 Red LED"))
    )
    (comp (ref "R21")
      (value "10K")
      (fields
        (field (name "BOM_Manufacturer Part") "ARG03FTC1002")
        (field (name "BOM_Supplier Part") "C217687")
      )
      (libsource (lib "") (part "ARG03FTC1002"))
    )
    (comp (ref "R22")
      (value "510")
      (fields
        (field (name "BOM_Manufacturer Part") "1206W4J0511T5E")
        (field (name "BOM_Supplier Part") "C25386")
      )
      (libsource (lib "") (part "1206W4J0511T5E"))
    )
    (comp (ref "R23")
      (value "510")
      (fields
        (field (name "BOM_Manufacturer Part") "1206W4J0511T5E")
        (field (name "BOM_Supplier Part") "C25386")
      )
      (libsource (lib "") (part "1206W4J0511T5E"))
    )
    (comp (ref "X3")
      (value "Header-Male-2.54_2x3")
      (fields (field (name "BOM_Supplier Part") "C65114"))
      (libsource (lib "") (part "Header-Male-2.54_2x3"))
    )
    (comp (ref "X4")
      (value "Header-Male-2.54_2x3")
      (fields (field (name "BOM_Supplier Part") "C65114"))
      (libsource (lib "") (part "Header-Male-2.54_2x3"))
    )
    (comp (ref "X5")
      (value "HDR-IDC-2.54-2X10P")
      (fields
        (field (name "BOM_Manufacturer Part") "IDC Box 2.54mm 2X10P　Straight")
        (field (name "BOM_Supplier Part") "C3405")
      )
      (libsource (lib "") (part "HDR-IDC-2.54-2X10P"))
    )
    (comp (ref "ZQ2")
      (value "16MHz")
      (fields
        (field (name "BOM_Manufacturer Part") "X49SD16MSB2SI")
        (field (name "BOM_Supplier Part") "C188202")
      )
      (libsource (lib "") (part "X49SD16MSB2SI"))
    )
    (comp (ref "C30")
      (value "10uF")
      (fields
        (field (name "BOM_Manufacturer Part") "CL31B106KOHNNNE")
        (field (name "BOM_Supplier Part") "C47971")
      )
      (libsource (lib "") (part "CL31B106KOHNNNE"))
    )
    (comp (ref "C31")
      (value "18pF")
      (fields
        (field (name "BOM_Manufacturer Part") "0402CG180J500NT")
        (field (name "BOM_Supplier Part") "C1549")
      )
      (libsource (lib "") (part "0402CG180J500NT"))
    )
    (comp (ref "C32")
      (value "18pF")
      (fields
        (field (name "BOM_Manufacturer Part") "0402CG180J500NT")
        (field (name "BOM_Supplier Part") "C1549")
      )
      (libsource (lib "") (part "0402CG180J500NT"))
    )
    (comp (ref "C33")
      (value "10nF")
      (fields
        (field (name "BOM_Manufacturer Part") "CL21B103KBANNNC")
        (field (name "BOM_Supplier Part") "C1710")
      )
      (libsource (lib "") (part "CL21B103KBANNNC"))
    )
    (comp (ref "C34")
      (value "10nF")
      (fields
        (field (name "BOM_Manufacturer Part") "CL21B103KBANNNC")
        (field (name "BOM_Supplier Part") "C1710")
      )
      (libsource (lib "") (part "CL21B103KBANNNC"))
    )
    (comp (ref "DD4")
      (value "ENC28J60-I/SO")
      (fields (field (name "BOM_Supplier Part") "C47351"))
      (libsource (lib "") (part "ENC28J60-I/SO"))
    )
    (comp (ref "H3")
      (value "Header-Male-2.54_1x2")
      (fields (field (name "BOM_Manufacturer Part") "826629-2") (field (name "BOM_Supplier Part") "C86471"))
      (libsource (lib "") (part "Header-Male-2.54_1x2"))
    )
    (comp (ref "H4")
      (value "Header-Male-2.54_1x2")
      (fields (field (name "BOM_Manufacturer Part") "826629-2") (field (name "BOM_Supplier Part") "C86471"))
      (libsource (lib "") (part "Header-Male-2.54_1x2"))
    )
    (comp (ref "L1")
      (value "10uH")
      (fields
        (field (name "BOM_Manufacturer Part") "CMI321609X100KT")
        (field (name "BOM_Supplier Part") "C1051")
      )
      (libsource (lib "") (part "CMI321609X100KT"))
    )
    (comp (ref "R24")
      (value "2.32K")
      (fields
        (field (name "BOM_Manufacturer Part") "1206W4F2321T5E")
        (field (name "BOM_Supplier Part") "C247348")
      )
      (libsource (lib "") (part "1206W4F2321T5E"))
    )
    (comp (ref "R25")
      (value "10K")
      (fields
        (field (name "BOM_Manufacturer Part") "ARG03FTC1002")
        (field (name "BOM_Supplier Part") "C217687")
      )
      (libsource (lib "") (part "ARG03FTC1002"))
    )
    (comp (ref "R26")
      (value "10K")
      (fields
        (field (name "BOM_Manufacturer Part") "ARG03FTC1002")
        (field (name "BOM_Supplier Part") "C217687")
      )
      (libsource (lib "") (part "ARG03FTC1002"))
    )
    (comp (ref "R27")
      (value "49.9")
      (fields
        (field (name "BOM_Manufacturer Part") "0805W8F499JT5E")
        (field (name "BOM_Supplier Part") "C17720")
      )
      (libsource (lib "") (part "0805W8F499JT5E"))
    )
    (comp (ref "R28")
      (value "49.9")
      (fields
        (field (name "BOM_Manufacturer Part") "0805W8F499JT5E")
        (field (name "BOM_Supplier Part") "C17720")
      )
      (libsource (lib "") (part "0805W8F499JT5E"))
    )
    (comp (ref "R29")
      (value "49.9")
      (fields
        (field (name "BOM_Manufacturer Part") "0805W8F499JT5E")
        (field (name "BOM_Supplier Part") "C17720")
      )
      (libsource (lib "") (part "0805W8F499JT5E"))
    )
    (comp (ref "R30")
      (value "49.9")
      (fields
        (field (name "BOM_Manufacturer Part") "0805W8F499JT5E")
        (field (name "BOM_Supplier Part") "C17720")
      )
      (libsource (lib "") (part "0805W8F499JT5E"))
    )
    (comp (ref "X6")
      (value "HR911105A_C12074")
      (fields (field (name "BOM_Manufacturer Part") "HR911105A") (field (name "BOM_Supplier Part") "C12074"))
      (libsource (lib "") (part "HR911105A_C12074"))
    )
    (comp (ref "ZQ3")
      (value "25MHz")
      (fields
        (field (name "BOM_Manufacturer Part") "X49SD25MSD2SI")
        (field (name "BOM_Supplier Part") "C130152")
      )
      (libsource (lib "") (part "X49SD25MSD2SI"))
    )
  )
  (nets
    (net (code "1") (name "3v3") (class "Default")
      (node (ref "C20") (pin "1") (pinfunction "1_1") (pintype "unspecified"))
      (node (ref "C7") (pin "2") (pinfunction "2_2") (pintype "input"))
      (node (ref "C8") (pin "1") (pinfunction "1_1") (pintype "unspecified"))
      (node (ref "C9") (pin "1") (pinfunction "1_1") (pintype "input"))
      (node (ref "DA1") (pin "2") (pinfunction "VOUT_2") (pintype "unspecified"))
      (node (ref "DA1") (pin "4") (pinfunction "VOUT_4") (pintype "unspecified"))
      (node (ref "DD1") (pin "2") (pinfunction "VDD33_2") (pintype "unspecified"))
      (node (ref "DD4") (pin "15") (pinfunction "VDDTX_15") (pintype "unspecified"))
      (node (ref "DD4") (pin "19") (pinfunction "VDDRX_19") (pintype "unspecified"))
      (node (ref "DD4") (pin "20") (pinfunction "VDDPLL_20") (pintype "unspecified"))
      (node (ref "DD4") (pin "25") (pinfunction "VDDOSC_25") (pintype "unspecified"))
      (node (ref "DD4") (pin "28") (pinfunction "VDD_28") (pintype "unspecified"))
      (node (ref "L1") (pin "1") (pinfunction "1_1") (pintype "unspecified"))
      (node (ref "R16") (pin "2") (pinfunction "2_2") (pintype "input"))
      (node (ref "R17") (pin "2") (pinfunction "2_2") (pintype "input"))
      (node (ref "R25") (pin "2") (pinfunction "2_2") (pintype "unspecified"))
      (node (ref "R26") (pin "2") (pinfunction "2_2") (pintype "unspecified"))
      (node (ref "U1") (pin "2") (pinfunction "VCCA_2") (pintype "unspecified"))
    )
    (net (code "2") (name "5V") (class "Default")
      (node (ref "C17") (pin "2") (pinfunction "2_2") (pintype "input"))
      (node (ref "C18") (pin "2") (pinfunction "2_2") (pintype "input"))
      (node (ref "C19") (pin "1") (pinfunction "1_1") (pintype "unspecified"))
      (node (ref "C26") (pin "1") (pinfunction "1_1") (pintype "unspecified"))
      (node (ref "C27") (pin "2") (pinfunction "2_2") (pintype "unspecified"))
      (node (ref "C28") (pin "1") (pinfunction "1_1") (pintype "unspecified"))
      (node (ref "D1") (pin "1") (pinfunction "K_1") (pintype "unspecified"))
      (node (ref "D2") (pin "1") (pinfunction "K_1") (pintype "unspecified"))
      (node (ref "DA1") (pin "3") (pinfunction "VIN_3") (pintype "unspecified"))
      (node (ref "DD2") (pin "16") (pinfunction "VCC_16") (pintype "unspecified"))
      (node (ref "DD3") (pin "21") (pinfunction "VCC_21") (pintype "unspecified"))
      (node (ref "DD3") (pin "52") (pinfunction "VCC_52") (pintype "unspecified"))
      (node (ref "DD3") (pin "64") (pinfunction "AVCC_64") (pintype "unspecified"))
      (node (ref "H2") (pin "1") (pinfunction "1_1") (pintype "unspecified"))
      (node (ref "R20") (pin "2") (pinfunction "2_2") (pintype "input"))
      (node (ref "R21") (pin "2") (pinfunction "2_2") (pintype "unspecified"))
      (node (ref "U1") (pin "19") (pinfunction "VCCB_19") (pintype "unspecified"))
      (node (ref "X3") (pin "2") (pinfunction "2_2") (pintype "input"))
      (node (ref "X4") (pin "2") (pinfunction "2_2") (pintype "input"))
    )
    (net (code "3") (name "5V_EXT") (class "Default")
      (node (ref "D2") (pin "2") (pinfunction "A_2") (pintype "unspecified"))
      (node (ref "H2") (pin "2") (pinfunction "2_2") (pintype "unspecified"))
      (node (ref "X1") (pin "1") (pinfunction "1_1") (pintype "unspecified"))
      (node (ref "X1") (pin "2") (pinfunction "2_2") (pintype "unspecified"))
    )
    (net (code "4") (name "AT_ADC0") (class "Default")
      (node (ref "DD3") (pin "61") (pinfunction "PF0(ADC0)_61") (pintype "unspecified"))
      (node (ref "X5") (pin "14") (pinfunction "14_14") (pintype "unspecified"))
    )
    (net (code "5") (name "AT_ADC1") (class "Default")
      (node (ref "DD3") (pin "60") (pinfunction "PF1(ADC1)_60") (pintype "unspecified"))
      (node (ref "X5") (pin "16") (pinfunction "16_16") (pintype "unspecified"))
    )
    (net (code "6") (name "AT_ADC2") (class "Default")
      (node (ref "DD3") (pin "59") (pinfunction "PF2(ADC2)_59") (pintype "unspecified"))
    )
    (net (code "7") (name "AT_ADC3") (class "Default")
      (node (ref "DD3") (pin "58") (pinfunction "PF3(ADC3)_58") (pintype "unspecified"))
    )
    (net (code "8") (name "AT_ADC4") (class "Default")
      (node (ref "DD3") (pin "57") (pinfunction "PF4(ADC4/TCK)_57") (pintype "unspecified"))
    )
    (net (code "9") (name "AT_BAT1") (class "Default")
      (node (ref "DD3") (pin "33") (pinfunction "PG0(WR#)_33") (pintype "unspecified"))
      (node (ref "X5") (pin "1") (pinfunction "1_1") (pintype "unspecified"))
    )
    (net (code "10") (name "AT_BAT2") (class "Default")
      (node (ref "DD3") (pin "34") (pinfunction "PG1(RD#)_34") (pintype "unspecified"))
      (node (ref "X5") (pin "2") (pinfunction "2_2") (pintype "unspecified"))
    )
    (net (code "11") (name "AT_BAT3") (class "Default")
      (node (ref "DD3") (pin "35") (pinfunction "PC0(A8)_35") (pintype "unspecified"))
      (node (ref "X5") (pin "3") (pinfunction "3_3") (pintype "unspecified"))
    )
    (net (code "12") (name "AT_BAT4") (class "Default")
      (node (ref "DD3") (pin "36") (pinfunction "PC1(A9)_36") (pintype "unspecified"))
      (node (ref "X5") (pin "4") (pinfunction "4_4") (pintype "unspecified"))
    )
    (net (code "13") (name "AT_BAT5") (class "Default")
      (node (ref "DD3") (pin "37") (pinfunction "PC2(A10)_37") (pintype "unspecified"))
      (node (ref "X5") (pin "5") (pinfunction "5_5") (pintype "unspecified"))
    )
    (net (code "14") (name "AT_BAT6") (class "Default")
      (node (ref "DD3") (pin "38") (pinfunction "PC3(A11)_38") (pintype "unspecified"))
      (node (ref "X5") (pin "6") (pinfunction "6_6") (pintype "unspecified"))
    )
    (net (code "15") (name "AT_BAT7") (class "Default")
      (node (ref "DD3") (pin "39") (pinfunction "PC4(A12)_39") (pintype "unspecified"))
      (node (ref "X5") (pin "7") (pinfunction "7_7") (pintype "unspecified"))
    )
    (net (code "16") (name "AT_BAT8") (class "Default")
      (node (ref "DD3") (pin "40") (pinfunction "PC5(A13)_40") (pintype "unspecified"))
      (node (ref "X5") (pin "8") (pinfunction "8_8") (pintype "unspecified"))
    )
    (net (code "17") (name "AT_BAT9") (class "Default")
      (node (ref "DD3") (pin "41") (pinfunction "PC6(A14)_41") (pintype "unspecified"))
      (node (ref "X5") (pin "9") (pinfunction "9_9") (pintype "unspecified"))
    )
    (net (code "18") (name "AT_BAT10") (class "Default")
      (node (ref "DD3") (pin "42") (pinfunction "PC7(A15)_42") (pintype "unspecified"))
      (node (ref "X5") (pin "10") (pinfunction "10_10") (pintype "unspecified"))
    )
    (net (code "19") (name "AT_BAT11") (class "Default")
      (node (ref "DD3") (pin "43") (pinfunction "PG2(ALE)_43") (pintype "unspecified"))
      (node (ref "X5") (pin "11") (pinfunction "11_11") (pintype "unspecified"))
    )
    (net (code "20") (name "AT_BAT12") (class "Default")
      (node (ref "DD3") (pin "44") (pinfunction "PA7(AD7)_44") (pintype "unspecified"))
      (node (ref "X5") (pin "12") (pinfunction "12_12") (pintype "unspecified"))
    )
    (net (code "21") (name "AT_INT4") (class "Default")
      (node (ref "DD3") (pin "6") (pinfunction "(OC3B/INT4)PE4_6") (pintype "unspecified"))
      (node (ref "KEY3") (pin "3") (pinfunction "3_3") (pintype "unspecified"))
    )
    (net (code "22") (name "AT_INT5") (class "Default")
      (node (ref "DD3") (pin "7") (pinfunction "(OC3C/INT5)PE5_7") (pintype "unspecified"))
      (node (ref "KEY4") (pin "2") (pinfunction "2_2") (pintype "unspecified"))
    )
    (net (code "23") (name "AT_MISO") (class "Default")
      (node (ref "DD3") (pin "13") (pinfunction "(MISO)PB3_13") (pintype "unspecified"))
      (node (ref "X3") (pin "1") (pinfunction "1_1") (pintype "input"))
    )
    (net (code "24") (name "AT_MOSI") (class "Default")
      (node (ref "DD3") (pin "12") (pinfunction "(MOSI)PB2_12") (pintype "unspecified"))
      (node (ref "X3") (pin "4") (pinfunction "4_4") (pintype "input"))
    )
    (net (code "25") (name "AT_OC0") (class "Default")
      (node (ref "DD3") (pin "14") (pinfunction "(OC0)PB4_14") (pintype "unspecified"))
    )
    (net (code "26") (name "AT_OC1A") (class "Default")
      (node (ref "DD3") (pin "15") (pinfunction "(OC1A)PB5_15") (pintype "unspecified"))
      (node (ref "X5") (pin "18") (pinfunction "18_18") (pintype "unspecified"))
    )
    (net (code "27") (name "AT_OC1B") (class "Default")
      (node (ref "DD3") (pin "16") (pinfunction "(OC1B)PB6_16") (pintype "unspecified"))
      (node (ref "X5") (pin "20") (pinfunction "20_20") (pintype "unspecified"))
    )
    (net (code "28") (name "AT_PD6") (class "Default")
      (node (ref "DD3") (pin "31") (pinfunction "(T1)PD6_31") (pintype "unspecified"))
      (node (ref "R22") (pin "1") (pinfunction "1_1") (pintype "input"))
    )
    (net (code "29") (name "AT_PD7") (class "Default")
      (node (ref "DD3") (pin "32") (pinfunction "(T2)PD7_32") (pintype "unspecified"))
      (node (ref "R23") (pin "1") (pinfunction "1_1") (pintype "input"))
    )
    (net (code "30") (name "AT_PDI") (class "Default")
      (node (ref "DD3") (pin "2") (pinfunction "RXD0/(PDI)PE0_2") (pintype "unspecified"))
      (node (ref "X4") (pin "4") (pinfunction "4_4") (pintype "input"))
    )
    (net (code "31") (name "AT_PDO") (class "Default")
      (node (ref "DD3") (pin "3") (pinfunction "(TXD0/PDO)PE1_3") (pintype "unspecified"))
      (node (ref "X4") (pin "1") (pinfunction "1_1") (pintype "input"))
    )
    (net (code "32") (name "AT_RESET") (class "Default")
      (node (ref "C25") (pin "2") (pinfunction "2_2") (pintype "input"))
      (node (ref "DD3") (pin "20") (pinfunction "RESET#_20") (pintype "unspecified"))
      (node (ref "R21") (pin "1") (pinfunction "1_1") (pintype "unspecified"))
      (node (ref "X3") (pin "5") (pinfunction "5_5") (pintype "input"))
      (node (ref "X4") (pin "5") (pinfunction "5_5") (pintype "input"))
    )
    (net (code "33") (name "AT_RXD1") (class "Default")
      (node (ref "DD3") (pin "27") (pinfunction "(RXD1/INT2)PD2_27") (pintype "unspecified"))
      (node (ref "U1") (pin "18") (pinfunction "B2_18") (pintype "unspecified"))
    )
    (net (code "34") (name "AT_SCK") (class "Default")
      (node (ref "DD3") (pin "11") (pinfunction "(SCK)PB1_11") (pintype "unspecified"))
      (node (ref "X3") (pin "3") (pinfunction "3_3") (pintype "input"))
      (node (ref "X4") (pin "3") (pinfunction "3_3") (pintype "input"))
    )
    (net (code "35") (name "AT_TXD1") (class "Default")
      (node (ref "DD3") (pin "28") (pinfunction "(TXD1/INT3)PD3_28") (pintype "unspecified"))
      (node (ref "U1") (pin "20") (pinfunction "B1_20") (pintype "unspecified"))
    )
    (net (code "36") (name "CLKOUT") (class "Default")
      (node (ref "DD4") (pin "3") (pinfunction "CLKOUT_3") (pintype "unspecified"))
    )
    (net (code "37") (name "CS") (class "Default")
      (node (ref "DD1") (pin "36") (pinfunction "IO22_36") (pintype "unspecified"))
      (node (ref "DD4") (pin "9") (pinfunction "CS#_9") (pintype "unspecified"))
      (node (ref "H4") (pin "2") (pinfunction "2_2") (pintype "unspecified"))
      (node (ref "R26") (pin "1") (pinfunction "1_1") (pintype "unspecified"))
    )
    (net (code "38") (name "DTR") (class "Default")
      (node (ref "DD2") (pin "13") (pinfunction "DTR#_13") (pintype "unspecified"))
      (node (ref "R14") (pin "1") (pinfunction "1_1") (pintype "input"))
      (node (ref "VT2") (pin "2") (pinfunction "2_2") (pintype "input"))
    )
    (net (code "39") (name "ESP_EN") (class "Default")
      (node (ref "C10") (pin "2") (pinfunction "2_2") (pintype "input"))
      (node (ref "C12") (pin "2") (pinfunction "2_2") (pintype "input"))
      (node (ref "DD1") (pin "3") (pinfunction "EN_3") (pintype "unspecified"))
      (node (ref "KEY1") (pin "2") (pinfunction "2_2") (pintype "unspecified"))
      (node (ref "R16") (pin "1") (pinfunction "1_1") (pintype "input"))
      (node (ref "VT1") (pin "3") (pinfunction "3_3") (pintype "input"))
    )
    (net (code "40") (name "ESP_IO0") (class "Default")
      (node (ref "C11") (pin "2") (pinfunction "2_2") (pintype "input"))
      (node (ref "C13") (pin "2") (pinfunction "2_2") (pintype "input"))
      (node (ref "DD1") (pin "25") (pinfunction "IO0_25") (pintype "unspecified"))
      (node (ref "H1") (pin "1") (pinfunction "1_1") (pintype "unspecified"))
      (node (ref "KEY2") (pin "2") (pinfunction "2_2") (pintype "unspecified"))
      (node (ref "VT2") (pin "3") (pinfunction "3_3") (pintype "input"))
    )
    (net (code "41") (name "ESP_IO4") (class "Default")
      (node (ref "DD1") (pin "26") (pinfunction "IO4_26") (pintype "unspecified"))
      (node (ref "DD4") (pin "4") (pinfunction "INT#_4") (pintype "unspecified"))
    )
    (net (code "42") (name "ESP_IO5") (class "Default")
      (node (ref "DD1") (pin "29") (pinfunction "IO5_29") (pintype "unspecified"))
      (node (ref "H4") (pin "1") (pinfunction "1_1") (pintype "unspecified"))
    )
    (net (code "43") (name "ESP_IO12") (class "Default")
      (node (ref "DD1") (pin "14") (pinfunction "IO12_14") (pintype "unspecified"))
      (node (ref "X1") (pin "19") (pinfunction "19_19") (pintype "unspecified"))
    )
    (net (code "44") (name "ESP_IO14") (class "Default")
      (node (ref "DD1") (pin "13") (pinfunction "IO14_13") (pintype "unspecified"))
      (node (ref "X1") (pin "20") (pinfunction "20_20") (pintype "unspecified"))
    )
    (net (code "45") (name "ESP_IO18") (class "Default")
      (node (ref "DD1") (pin "30") (pinfunction "IO18_30") (pintype "unspecified"))
      (node (ref "H3") (pin "1") (pinfunction "1_1") (pintype "unspecified"))
    )
    (net (code "46") (name "ESP_IO19") (class "Default")
      (node (ref "DD1") (pin "31") (pinfunction "IO19_31") (pintype "unspecified"))
      (node (ref "DD4") (pin "8") (pinfunction "SCK_8") (pintype "unspecified"))
    )
    (net (code "47") (name "ESP_IO21") (class "Default")
      (node (ref "C9") (pin "2") (pinfunction "2_2") (pintype "input"))
      (node (ref "DD1") (pin "33") (pinfunction "IO21_33") (pintype "unspecified"))
      (node (ref "R13") (pin "2") (pinfunction "2_2") (pintype "unspecified"))
      (node (ref "U1") (pin "10") (pinfunction "OE_10") (pintype "unspecified"))
    )
    (net (code "48") (name "ESP_IO23") (class "Default")
      (node (ref "DD1") (pin "37") (pinfunction "IO23_37") (pintype "unspecified"))
      (node (ref "DD4") (pin "7") (pinfunction "SI_7") (pintype "unspecified"))
    )
    (net (code "49") (name "ESP_IO25") (class "Default")
      (node (ref "DD1") (pin "10") (pinfunction "IO25_10") (pintype "unspecified"))
      (node (ref "DD4") (pin "6") (pinfunction "SO_6") (pintype "unspecified"))
    )
    (net (code "50") (name "ESP_IO26") (class "Default")
      (node (ref "DD1") (pin "11") (pinfunction "IO26_11") (pintype "unspecified"))
      (node (ref "X1") (pin "16") (pinfunction "16_16") (pintype "unspecified"))
    )
    (net (code "51") (name "ESP_IO27") (class "Default")
      (node (ref "DD1") (pin "12") (pinfunction "IO27_12") (pintype "unspecified"))
      (node (ref "X1") (pin "18") (pinfunction "18_18") (pintype "unspecified"))
    )
    (net (code "52") (name "ESP_IO32") (class "Default")
      (node (ref "C4") (pin "1") (pinfunction "1_1") (pintype "input"))
      (node (ref "DD1") (pin "8") (pinfunction "IO32_8") (pintype "unspecified"))
      (node (ref "R7") (pin "1") (pinfunction "1_1") (pintype "input"))
      (node (ref "R8") (pin "2") (pinfunction "2_2") (pintype "input"))
    )
    (net (code "53") (name "ESP_IO33") (class "Default")
      (node (ref "C2") (pin "1") (pinfunction "1_1") (pintype "input"))
      (node (ref "DD1") (pin "9") (pinfunction "IO33_9") (pintype "unspecified"))
      (node (ref "R3") (pin "1") (pinfunction "1_1") (pintype "input"))
      (node (ref "R4") (pin "2") (pinfunction "2_2") (pintype "input"))
    )
    (net (code "54") (name "ESP_IO34") (class "Default")
      (node (ref "C5") (pin "1") (pinfunction "1_1") (pintype "input"))
      (node (ref "DD1") (pin "6") (pinfunction "IO34_6") (pintype "unspecified"))
      (node (ref "R10") (pin "2") (pinfunction "2_2") (pintype "input"))
      (node (ref "R9") (pin "1") (pinfunction "1_1") (pintype "input"))
    )
    (net (code "55") (name "ESP_IO35") (class "Default")
      (node (ref "C6") (pin "1") (pinfunction "1_1") (pintype "input"))
      (node (ref "DD1") (pin "7") (pinfunction "IO35_7") (pintype "unspecified"))
      (node (ref "R11") (pin "1") (pinfunction "1_1") (pintype "input"))
      (node (ref "R12") (pin "2") (pinfunction "2_2") (pintype "input"))
    )
    (net (code "56") (name "ESP_IO36") (class "Default")
      (node (ref "C1") (pin "1") (pinfunction "1_1") (pintype "input"))
      (node (ref "DD1") (pin "4") (pinfunction "SENSOR_VP_4") (pintype "unspecified"))
      (node (ref "R1") (pin "1") (pinfunction "1_1") (pintype "input"))
      (node (ref "R2") (pin "2") (pinfunction "2_2") (pintype "input"))
    )
    (net (code "57") (name "ESP_IO39") (class "Default")
      (node (ref "C3") (pin "1") (pinfunction "1_1") (pintype "input"))
      (node (ref "DD1") (pin "5") (pinfunction "SENSOR_VN_5") (pintype "unspecified"))
      (node (ref "R5") (pin "1") (pinfunction "1_1") (pintype "input"))
      (node (ref "R6") (pin "2") (pinfunction "2_2") (pintype "input"))
    )
    (net (code "58") (name "ESP_RXD0") (class "Default")
      (node (ref "DD1") (pin "34") (pinfunction "RXD0_34") (pintype "unspecified"))
      (node (ref "R18") (pin "2") (pinfunction "2_2") (pintype "input"))
    )
    (net (code "59") (name "ESP_TXD0") (class "Default")
      (node (ref "DD1") (pin "35") (pinfunction "TXD0_35") (pintype "unspecified"))
      (node (ref "R19") (pin "2") (pinfunction "2_2") (pintype "input"))
    )
    (net (code "60") (name "ESP_U2RXD") (class "Default")
      (node (ref "DD1") (pin "27") (pinfunction "IO16_27") (pintype "unspecified"))
      (node (ref "U1") (pin "1") (pinfunction "A1_1") (pintype "unspecified"))
    )
    (net (code "61") (name "ESP_U2TXD") (class "Default")
      (node (ref "DD1") (pin "28") (pinfunction "IO17_28") (pintype "unspecified"))
      (node (ref "U1") (pin "3") (pinfunction "A2_3") (pintype "unspecified"))
    )
    (net (code "62") (name "GND") (class "Default")
      (node (ref "C1") (pin "2") (pinfunction "2_2") (pintype "input"))
      (node (ref "C10") (pin "1") (pinfunction "1_1") (pintype "input"))
      (node (ref "C11") (pin "1") (pinfunction "1_1") (pintype "input"))
      (node (ref "C14") (pin "1") (pinfunction "1_1") (pintype "input"))
      (node (ref "C15") (pin "1") (pinfunction "1_1") (pintype "input"))
      (node (ref "C16") (pin "1") (pinfunction "1_1") (pintype "input"))
      (node (ref "C17") (pin "1") (pinfunction "1_1") (pintype "input"))
      (node (ref "C18") (pin "1") (pinfunction "1_1") (pintype "input"))
      (node (ref "C19") (pin "2") (pinfunction "2_2") (pintype "unspecified"))
      (node (ref "C2") (pin "2") (pinfunction "2_2") (pintype "input"))
      (node (ref "C20") (pin "2") (pinfunction "2_2") (pintype "unspecified"))
      (node (ref "C21") (pin "1") (pinfunction "1_1") (pintype "input"))
      (node (ref "C22") (pin "1") (pinfunction "1_1") (pintype "input"))
      (node (ref "C23") (pin "2") (pinfunction "2_2") (pintype "input"))
      (node (ref "C24") (pin "1") (pinfunction "1_1") (pintype "input"))
      (node (ref "C25") (pin "1") (pinfunction "1_1") (pintype "input"))
      (node (ref "C26") (pin "2") (pinfunction "2_2") (pintype "unspecified"))
      (node (ref "C27") (pin "1") (pinfunction "1_1") (pintype "unspecified"))
      (node (ref "C28") (pin "2") (pinfunction "2_2") (pintype "unspecified"))
      (node (ref "C29") (pin "1") (pinfunction "1_1") (pintype "input"))
      (node (ref "C3") (pin "2") (pinfunction "2_2") (pintype "input"))
      (node (ref "C30") (pin "2") (pinfunction "2_2") (pintype "input"))
      (node (ref "C31") (pin "2") (pinfunction "2_2") (pintype "input"))
      (node (ref "C32") (pin "2") (pinfunction "2_2") (pintype "input"))
      (node (ref "C33") (pin "2") (pinfunction "2_2") (pintype "input"))
      (node (ref "C34") (pin "2") (pinfunction "2_2") (pintype "input"))
      (node (ref "C4") (pin "2") (pinfunction "2_2") (pintype "input"))
      (node (ref "C5") (pin "2") (pinfunction "2_2") (pintype "input"))
      (node (ref "C6") (pin "2") (pinfunction "2_2") (pintype "input"))
      (node (ref "C7") (pin "1") (pinfunction "1_1") (pintype "input"))
      (node (ref "C8") (pin "2") (pinfunction "2_2") (pintype "unspecified"))
      (node (ref "DA1") (pin "1") (pinfunction "ADJ/GND_1") (pintype "unspecified"))
      (node (ref "DD1") (pin "1") (pinfunction "GND_1") (pintype "unspecified"))
      (node (ref "DD1") (pin "15") (pinfunction "GND_15") (pintype "unspecified"))
      (node (ref "DD1") (pin "38") (pinfunction "GND_38") (pintype "unspecified"))
      (node (ref "DD1") (pin "39") (pinfunction "GND_39") (pintype "unspecified"))
      (node (ref "DD2") (pin "1") (pinfunction "GND_1") (pintype "unspecified"))
      (node (ref "DD3") (pin "22") (pinfunction "GND_22") (pintype "unspecified"))
      (node (ref "DD3") (pin "53") (pinfunction "GND_53") (pintype "unspecified"))
      (node (ref "DD3") (pin "63") (pinfunction "GND_63") (pintype "unspecified"))
      (node (ref "DD4") (pin "11") (pinfunction "VSSRX_11") (pintype "unspecified"))
      (node (ref "DD4") (pin "18") (pinfunction "VSSTX_18") (pintype "unspecified"))
      (node (ref "DD4") (pin "2") (pinfunction "VSS_2") (pintype "unspecified"))
      (node (ref "DD4") (pin "21") (pinfunction "VSSPLL_21") (pintype "unspecified"))
      (node (ref "DD4") (pin "22") (pinfunction "VSSOSC_22") (pintype "unspecified"))
      (node (ref "KEY1") (pin "4") (pinfunction "4_4") (pintype "unspecified"))
      (node (ref "KEY2") (pin "4") (pinfunction "4_4") (pintype "unspecified"))
      (node (ref "KEY3") (pin "4") (pinfunction "4_4") (pintype "unspecified"))
      (node (ref "KEY4") (pin "1") (pinfunction "1_1") (pintype "unspecified"))
      (node (ref "LED1") (pin "2") (pinfunction "K_2") (pintype "unspecified"))
      (node (ref "LED2") (pin "2") (pinfunction "K_2") (pintype "unspecified"))
      (node (ref "LED3") (pin "2") (pinfunction "K_2") (pintype "unspecified"))
      (node (ref "R1") (pin "2") (pinfunction "2_2") (pintype "input"))
      (node (ref "R12") (pin "1") (pinfunction "1_1") (pintype "input"))
      (node (ref "R13") (pin "1") (pinfunction "1_1") (pintype "unspecified"))
      (node (ref "R24") (pin "1") (pinfunction "1_1") (pintype "unspecified"))
      (node (ref "R4") (pin "1") (pinfunction "1_1") (pintype "input"))
      (node (ref "R5") (pin "2") (pinfunction "2_2") (pintype "input"))
      (node (ref "R8") (pin "1") (pinfunction "1_1") (pintype "input"))
      (node (ref "R9") (pin "2") (pinfunction "2_2") (pintype "input"))
      (node (ref "U1") (pin "11") (pinfunction "GND_11") (pintype "unspecified"))
      (node (ref "X1") (pin "11") (pinfunction "11_11") (pintype "unspecified"))
      (node (ref "X1") (pin "13") (pinfunction "13_13") (pintype "unspecified"))
      (node (ref "X1") (pin "15") (pinfunction "15_15") (pintype "unspecified"))
      (node (ref "X1") (pin "17") (pinfunction "17_17") (pintype "unspecified"))
      (node (ref "X1") (pin "3") (pinfunction "3_3") (pintype "unspecified"))
      (node (ref "X1") (pin "5") (pinfunction "5_5") (pintype "unspecified"))
      (node (ref "X1") (pin "7") (pinfunction "7_7") (pintype "unspecified"))
      (node (ref "X1") (pin "9") (pinfunction "9_9") (pintype "unspecified"))
      (node (ref "X2") (pin "5") (pinfunction "GND_5") (pintype "unspecified"))
      (node (ref "X2") (pin "6") (pinfunction "SH1_6") (pintype "unspecified"))
      (node (ref "X2") (pin "7") (pinfunction "SH2_7") (pintype "unspecified"))
      (node (ref "X2") (pin "8") (pinfunction "SH3_8") (pintype "unspecified"))
      (node (ref "X2") (pin "9") (pinfunction "SH4_9") (pintype "unspecified"))
      (node (ref "X3") (pin "6") (pinfunction "6_6") (pintype "input"))
      (node (ref "X4") (pin "6") (pinfunction "6_6") (pintype "input"))
      (node (ref "X5") (pin "13") (pinfunction "13_13") (pintype "unspecified"))
      (node (ref "X5") (pin "15") (pinfunction "15_15") (pintype "unspecified"))
      (node (ref "X5") (pin "17") (pinfunction "17_17") (pintype "unspecified"))
      (node (ref "X5") (pin "19") (pinfunction "19_19") (pintype "unspecified"))
      (node (ref "X6") (pin "10") (pinfunction "10_10") (pintype "unspecified"))
      (node (ref "X6") (pin "11") (pinfunction "11_11") (pintype "unspecified"))
      (node (ref "X6") (pin "SH1") (pinfunction "SH1_SH1") (pintype "unspecified"))
      (node (ref "X6") (pin "SH2") (pinfunction "SH2_SH2") (pintype "unspecified"))
    )
    (net (code "63") (name "LEDA") (class "Default")
      (node (ref "DD4") (pin "27") (pinfunction "LEDA_27") (pintype "unspecified"))
      (node (ref "X6") (pin "9") (pinfunction "9_9") (pintype "unspecified"))
    )
    (net (code "64") (name "LEDB") (class "Default")
      (node (ref "DD4") (pin "26") (pinfunction "LEDB_26") (pintype "unspecified"))
      (node (ref "X6") (pin "12") (pinfunction "12_12") (pintype "unspecified"))
    )
    (net (code "65") (name "Net-(C12-Pad1)") (class "Default")
      (node (ref "C12") (pin "1") (pinfunction "1_1") (pintype "input"))
      (node (ref "KEY1") (pin "1") (pinfunction "1_1") (pintype "unspecified"))
    )
    (net (code "66") (name "Net-(C13-Pad1)") (class "Default")
      (node (ref "C13") (pin "1") (pinfunction "1_1") (pintype "input"))
      (node (ref "KEY2") (pin "1") (pinfunction "1_1") (pintype "unspecified"))
    )
    (net (code "67") (name "Net-(C21-Pad2)") (class "Default")
      (node (ref "C21") (pin "2") (pinfunction "2_2") (pintype "input"))
      (node (ref "KEY3") (pin "2") (pinfunction "2_2") (pintype "unspecified"))
    )
    (net (code "68") (name "Net-(C22-Pad2)") (class "Default")
      (node (ref "C22") (pin "2") (pinfunction "2_2") (pintype "input"))
      (node (ref "KEY4") (pin "3") (pinfunction "3_3") (pintype "unspecified"))
    )
    (net (code "69") (name "Net-(C33-Pad1)") (class "Default")
      (node (ref "C33") (pin "1") (pinfunction "1_1") (pintype "input"))
      (node (ref "R27") (pin "1") (pinfunction "1_1") (pintype "input"))
      (node (ref "R28") (pin "2") (pinfunction "2_2") (pintype "input"))
      (node (ref "X6") (pin "5") (pinfunction "5_5") (pintype "unspecified"))
    )
    (net (code "70") (name "Net-(C34-Pad1)") (class "Default")
      (node (ref "C34") (pin "1") (pinfunction "1_1") (pintype "input"))
      (node (ref "L1") (pin "2") (pinfunction "2_2") (pintype "unspecified"))
      (node (ref "R29") (pin "1") (pinfunction "1_1") (pintype "input"))
      (node (ref "R30") (pin "2") (pinfunction "2_2") (pintype "input"))
      (node (ref "X6") (pin "4") (pinfunction "4_4") (pintype "unspecified"))
    )
    (net (code "71") (name "Net-(D1-A)") (class "Default")
      (node (ref "D1") (pin "2") (pinfunction "A_2") (pintype "unspecified"))
      (node (ref "X2") (pin "1") (pinfunction "VBUS_1") (pintype "unspecified"))
    )
    (net (code "72") (name "Net-(DD2-RXD)") (class "Default")
      (node (ref "DD2") (pin "3") (pinfunction "RXD_3") (pintype "unspecified"))
      (node (ref "R18") (pin "1") (pinfunction "1_1") (pintype "input"))
    )
    (net (code "73") (name "Net-(DD2-TXD)") (class "Default")
      (node (ref "DD2") (pin "2") (pinfunction "TXD_2") (pintype "unspecified"))
      (node (ref "R19") (pin "1") (pinfunction "1_1") (pintype "input"))
    )
    (net (code "74") (name "Net-(DD2-UD+)") (class "Default")
      (node (ref "DD2") (pin "5") (pinfunction "UD+_5") (pintype "unspecified"))
      (node (ref "X2") (pin "3") (pinfunction "D+_3") (pintype "unspecified"))
    )
    (net (code "75") (name "Net-(DD2-UD-)") (class "Default")
      (node (ref "DD2") (pin "6") (pinfunction "UD-_6") (pintype "unspecified"))
      (node (ref "X2") (pin "2") (pinfunction "D-_2") (pintype "unspecified"))
    )
    (net (code "76") (name "Net-(DD2-V3)") (class "Default")
      (node (ref "C14") (pin "2") (pinfunction "2_2") (pintype "input"))
      (node (ref "DD2") (pin "4") (pinfunction "V3_4") (pintype "unspecified"))
    )
    (net (code "77") (name "Net-(DD2-XI)") (class "Default")
      (node (ref "C15") (pin "2") (pinfunction "2_2") (pintype "input"))
      (node (ref "DD2") (pin "7") (pinfunction "XI_7") (pintype "unspecified"))
      (node (ref "ZQ1") (pin "1") (pinfunction "1_1") (pintype "unspecified"))
    )
    (net (code "78") (name "Net-(DD2-XO)") (class "Default")
      (node (ref "C16") (pin "2") (pinfunction "2_2") (pintype "input"))
      (node (ref "DD2") (pin "8") (pinfunction "XO_8") (pintype "unspecified"))
      (node (ref "ZQ1") (pin "2") (pinfunction "2_2") (pintype "unspecified"))
    )
    (net (code "79") (name "Net-(DD3-AREF)") (class "Default")
      (node (ref "C29") (pin "2") (pinfunction "2_2") (pintype "input"))
      (node (ref "DD3") (pin "62") (pinfunction "AREF_62") (pintype "unspecified"))
    )
    (net (code "80") (name "Net-(DD3-XTAL1)") (class "Default")
      (node (ref "C24") (pin "2") (pinfunction "2_2") (pintype "input"))
      (node (ref "DD3") (pin "24") (pinfunction "XTAL1_24") (pintype "unspecified"))
      (node (ref "ZQ2") (pin "1") (pinfunction "OSC1_1") (pintype "input"))
    )
    (net (code "81") (name "Net-(DD3-XTAL2)") (class "Default")
      (node (ref "C23") (pin "1") (pinfunction "1_1") (pintype "input"))
      (node (ref "DD3") (pin "23") (pinfunction "XTAL2_23") (pintype "unspecified"))
      (node (ref "ZQ2") (pin "2") (pinfunction "OSC2_2") (pintype "input"))
    )
    (net (code "82") (name "Net-(DD4-OSC1)") (class "Default")
      (node (ref "C31") (pin "1") (pinfunction "1_1") (pintype "input"))
      (node (ref "DD4") (pin "23") (pinfunction "OSC1_23") (pintype "unspecified"))
      (node (ref "ZQ3") (pin "1") (pinfunction "1_1") (pintype "unspecified"))
    )
    (net (code "83") (name "Net-(DD4-OSC2)") (class "Default")
      (node (ref "C32") (pin "1") (pinfunction "1_1") (pintype "input"))
      (node (ref "DD4") (pin "24") (pinfunction "OSC2_24") (pintype "unspecified"))
      (node (ref "ZQ3") (pin "2") (pinfunction "2_2") (pintype "unspecified"))
    )
    (net (code "84") (name "Net-(DD4-RBIAS)") (class "Default")
      (node (ref "DD4") (pin "14") (pinfunction "RBIAS_14") (pintype "unspecified"))
      (node (ref "R24") (pin "2") (pinfunction "2_2") (pintype "unspecified"))
    )
    (net (code "85") (name "Net-(DD4-VCAP)") (class "Default")
      (node (ref "C30") (pin "1") (pinfunction "1_1") (pintype "input"))
      (node (ref "DD4") (pin "1") (pinfunction "VCAP_1") (pintype "unspecified"))
    )
    (net (code "86") (name "Net-(H1-Pad2)") (class "Default")
      (node (ref "H1") (pin "2") (pinfunction "2_2") (pintype "unspecified"))
      (node (ref "R17") (pin "1") (pinfunction "1_1") (pintype "input"))
    )
    (net (code "87") (name "Net-(LED1-A)") (class "Default")
      (node (ref "LED1") (pin "1") (pinfunction "A_1") (pintype "unspecified"))
      (node (ref "R20") (pin "1") (pinfunction "1_1") (pintype "input"))
    )
    (net (code "88") (name "Net-(LED2-A)") (class "Default")
      (node (ref "LED2") (pin "1") (pinfunction "A_1") (pintype "unspecified"))
      (node (ref "R22") (pin "2") (pinfunction "2_2") (pintype "input"))
    )
    (net (code "89") (name "Net-(LED3-A)") (class "Default")
      (node (ref "LED3") (pin "1") (pinfunction "A_1") (pintype "unspecified"))
      (node (ref "R23") (pin "2") (pinfunction "2_2") (pintype "input"))
    )
    (net (code "90") (name "Net-(R2-Pad1)") (class "Default")
      (node (ref "R2") (pin "1") (pinfunction "1_1") (pintype "input"))
      (node (ref "X1") (pin "4") (pinfunction "4_4") (pintype "unspecified"))
    )
    (net (code "91") (name "Net-(R3-Pad2)") (class "Default")
      (node (ref "R3") (pin "2") (pinfunction "2_2") (pintype "input"))
      (node (ref "X1") (pin "14") (pinfunction "14_14") (pintype "unspecified"))
    )
    (net (code "92") (name "Net-(R6-Pad1)") (class "Default")
      (node (ref "R6") (pin "1") (pinfunction "1_1") (pintype "input"))
      (node (ref "X1") (pin "6") (pinfunction "6_6") (pintype "unspecified"))
    )
    (net (code "93") (name "Net-(R7-Pad2)") (class "Default")
      (node (ref "R7") (pin "2") (pinfunction "2_2") (pintype "input"))
      (node (ref "X1") (pin "12") (pinfunction "12_12") (pintype "unspecified"))
    )
    (net (code "94") (name "Net-(R10-Pad1)") (class "Default")
      (node (ref "R10") (pin "1") (pinfunction "1_1") (pintype "input"))
      (node (ref "X1") (pin "8") (pinfunction "8_8") (pintype "unspecified"))
    )
    (net (code "95") (name "Net-(R11-Pad2)") (class "Default")
      (node (ref "R11") (pin "2") (pinfunction "2_2") (pintype "input"))
      (node (ref "X1") (pin "10") (pinfunction "10_10") (pintype "unspecified"))
    )
    (net (code "96") (name "Net-(R14-Pad2)") (class "Default")
      (node (ref "R14") (pin "2") (pinfunction "2_2") (pintype "input"))
      (node (ref "VT1") (pin "1") (pinfunction "1_1") (pintype "input"))
    )
    (net (code "97") (name "Net-(R15-Pad1)") (class "Default")
      (node (ref "R15") (pin "1") (pinfunction "1_1") (pintype "input"))
      (node (ref "VT2") (pin "1") (pinfunction "1_1") (pintype "input"))
    )
    (net (code "98") (name "RESET") (class "Default")
      (node (ref "DD4") (pin "10") (pinfunction "RESET#_10") (pintype "unspecified"))
      (node (ref "H3") (pin "2") (pinfunction "2_2") (pintype "unspecified"))
      (node (ref "R25") (pin "1") (pinfunction "1_1") (pintype "unspecified"))
    )
    (net (code "99") (name "RTS") (class "Default")
      (node (ref "DD2") (pin "14") (pinfunction "RTS#_14") (pintype "unspecified"))
      (node (ref "R15") (pin "2") (pinfunction "2_2") (pintype "input"))
      (node (ref "VT1") (pin "2") (pinfunction "2_2") (pintype "input"))
    )
    (net (code "100") (name "TPIN+") (class "Default")
      (node (ref "DD4") (pin "13") (pinfunction "TPIN+_13") (pintype "unspecified"))
      (node (ref "R28") (pin "1") (pinfunction "1_1") (pintype "input"))
      (node (ref "X6") (pin "3") (pinfunction "RD+_3") (pintype "unspecified"))
    )
    (net (code "101") (name "TPIN-") (class "Default")
      (node (ref "DD4") (pin "12") (pinfunction "TPIN-_12") (pintype "unspecified"))
      (node (ref "R27") (pin "2") (pinfunction "2_2") (pintype "input"))
      (node (ref "X6") (pin "6") (pinfunction "RD-_6") (pintype "unspecified"))
    )
    (net (code "102") (name "TPOUT+") (class "Default")
      (node (ref "DD4") (pin "17") (pinfunction "TPOUT+_17") (pintype "unspecified"))
      (node (ref "R30") (pin "1") (pinfunction "1_1") (pintype "input"))
      (node (ref "X6") (pin "1") (pinfunction "TD+_1") (pintype "unspecified"))
    )
    (net (code "103") (name "TPOUT-") (class "Default")
      (node (ref "DD4") (pin "16") (pinfunction "TPOUT-_16") (pintype "unspecified"))
      (node (ref "R29") (pin "2") (pinfunction "2_2") (pintype "input"))
      (node (ref "X6") (pin "2") (pinfunction "TD-_2") (pintype "unspecified"))
    )
    (net (code "104") (name "unconnected-(DD1-CLK-Pad20)") (class "Default")
      (node (ref "DD1") (pin "20") (pinfunction "CLK_20") (pintype "unspecified"))
    )
    (net (code "105") (name "unconnected-(DD1-CMD-Pad19)") (class "Default")
      (node (ref "DD1") (pin "19") (pinfunction "CMD_19") (pintype "unspecified"))
    )
    (net (code "106") (name "unconnected-(DD1-IO2-Pad24)") (class "Default")
      (node (ref "DD1") (pin "24") (pinfunction "IO2_24") (pintype "unspecified"))
    )
    (net (code "107") (name "unconnected-(DD1-IO13-Pad16)") (class "Default")
      (node (ref "DD1") (pin "16") (pinfunction "IO13_16") (pintype "unspecified"))
    )
    (net (code "108") (name "unconnected-(DD1-IO15-Pad23)") (class "Default")
      (node (ref "DD1") (pin "23") (pinfunction "IO15_23") (pintype "unspecified"))
    )
    (net (code "109") (name "unconnected-(DD1-NC-Pad32)") (class "Default")
      (node (ref "DD1") (pin "32") (pinfunction "NC_32") (pintype "unspecified"))
    )
    (net (code "110") (name "unconnected-(DD1-SD0-Pad21)") (class "Default")
      (node (ref "DD1") (pin "21") (pinfunction "SD0_21") (pintype "unspecified"))
    )
    (net (code "111") (name "unconnected-(DD1-SD1-Pad22)") (class "Default")
      (node (ref "DD1") (pin "22") (pinfunction "SD1_22") (pintype "unspecified"))
    )
    (net (code "112") (name "unconnected-(DD1-SD2-Pad17)") (class "Default")
      (node (ref "DD1") (pin "17") (pinfunction "SD2_17") (pintype "unspecified"))
    )
    (net (code "113") (name "unconnected-(DD1-SD3-Pad18)") (class "Default")
      (node (ref "DD1") (pin "18") (pinfunction "SD3_18") (pintype "unspecified"))
    )
    (net (code "114") (name "unconnected-(DD2-CTS#-Pad9)") (class "Default")
      (node (ref "DD2") (pin "9") (pinfunction "CTS#_9") (pintype "unspecified"))
    )
    (net (code "115") (name "unconnected-(DD2-DCD#-Pad12)") (class "Default")
      (node (ref "DD2") (pin "12") (pinfunction "DCD#_12") (pintype "unspecified"))
    )
    (net (code "116") (name "unconnected-(DD2-DSR#-Pad10)") (class "Default")
      (node (ref "DD2") (pin "10") (pinfunction "DSR#_10") (pintype "unspecified"))
    )
    (net (code "117") (name "unconnected-(DD2-R232-Pad15)") (class "Default")
      (node (ref "DD2") (pin "15") (pinfunction "R232_15") (pintype "unspecified"))
    )
    (net (code "118") (name "unconnected-(DD2-RI-Pad11)") (class "Default")
      (node (ref "DD2") (pin "11") (pinfunction "RI_11") (pintype "unspecified"))
    )
    (net (code "119") (name "unconnected-(DD3-(ICP1)PD4-Pad29)") (class "Default")
      (node (ref "DD3") (pin "29") (pinfunction "(ICP1)PD4_29") (pintype "unspecified"))
    )
    (net (code "120") (name "unconnected-(DD3-(ICP3{slash}INT7)PE7-Pad9)") (class "Default")
      (node (ref "DD3") (pin "9") (pinfunction "(ICP3/INT7)PE7_9") (pintype "unspecified"))
    )
    (net (code "121") (name "unconnected-(DD3-(OC2{slash}OC1C)PB7-Pad17)") (class "Default")
      (node (ref "DD3") (pin "17") (pinfunction "(OC2/OC1C)PB7_17") (pintype "unspecified"))
    )
    (net (code "122") (name "unconnected-(DD3-(OC3A{slash}AIN1)PE3-Pad5)") (class "Default")
      (node (ref "DD3") (pin "5") (pinfunction "(OC3A/AIN1)PE3_5") (pintype "unspecified"))
    )
    (net (code "123") (name "unconnected-(DD3-(SCL{slash}INT0)PD0-Pad25)") (class "Default")
      (node (ref "DD3") (pin "25") (pinfunction "(SCL/INT0)PD0_25") (pintype "unspecified"))
    )
    (net (code "124") (name "unconnected-(DD3-(SDA{slash}INT1)PD1-Pad26)") (class "Default")
      (node (ref "DD3") (pin "26") (pinfunction "(SDA/INT1)PD1_26") (pintype "unspecified"))
    )
    (net (code "125") (name "unconnected-(DD3-(SS#)PB0-Pad10)") (class "Default")
      (node (ref "DD3") (pin "10") (pinfunction "(SS#)PB0_10") (pintype "unspecified"))
    )
    (net (code "126") (name "unconnected-(DD3-(T3{slash}INT6)PE6-Pad8)") (class "Default")
      (node (ref "DD3") (pin "8") (pinfunction "(T3/INT6)PE6_8") (pintype "unspecified"))
    )
    (net (code "127") (name "unconnected-(DD3-(XCK0{slash}AIN0)PE2-Pad4)") (class "Default")
      (node (ref "DD3") (pin "4") (pinfunction "(XCK0/AIN0)PE2_4") (pintype "unspecified"))
    )
    (net (code "128") (name "unconnected-(DD3-(XCK1)PD5-Pad30)") (class "Default")
      (node (ref "DD3") (pin "30") (pinfunction "(XCK1)PD5_30") (pintype "unspecified"))
    )
    (net (code "129") (name "unconnected-(DD3-PA0(AD0)-Pad51)") (class "Default")
      (node (ref "DD3") (pin "51") (pinfunction "PA0(AD0)_51") (pintype "unspecified"))
    )
    (net (code "130") (name "unconnected-(DD3-PA1(AD1)-Pad50)") (class "Default")
      (node (ref "DD3") (pin "50") (pinfunction "PA1(AD1)_50") (pintype "unspecified"))
    )
    (net (code "131") (name "unconnected-(DD3-PA2(AD2)-Pad49)") (class "Default")
      (node (ref "DD3") (pin "49") (pinfunction "PA2(AD2)_49") (pintype "unspecified"))
    )
    (net (code "132") (name "unconnected-(DD3-PA3(AD3)-Pad48)") (class "Default")
      (node (ref "DD3") (pin "48") (pinfunction "PA3(AD3)_48") (pintype "unspecified"))
    )
    (net (code "133") (name "unconnected-(DD3-PA4(AD4)-Pad47)") (class "Default")
      (node (ref "DD3") (pin "47") (pinfunction "PA4(AD4)_47") (pintype "unspecified"))
    )
    (net (code "134") (name "unconnected-(DD3-PA5(AD5)-Pad46)") (class "Default")
      (node (ref "DD3") (pin "46") (pinfunction "PA5(AD5)_46") (pintype "unspecified"))
    )
    (net (code "135") (name "unconnected-(DD3-PA6(AD6)-Pad45)") (class "Default")
      (node (ref "DD3") (pin "45") (pinfunction "PA6(AD6)_45") (pintype "unspecified"))
    )
    (net (code "136") (name "unconnected-(DD3-PEN#-Pad1)") (class "Default")
      (node (ref "DD3") (pin "1") (pinfunction "PEN#_1") (pintype "unspecified"))
    )
    (net (code "137") (name "unconnected-(DD3-PF5(ADC5{slash}TMS)-Pad56)") (class "Default")
      (node (ref "DD3") (pin "56") (pinfunction "PF5(ADC5/TMS)_56") (pintype "unspecified"))
    )
    (net (code "138") (name "unconnected-(DD3-PF6(ADC6{slash}TDO)-Pad55)") (class "Default")
      (node (ref "DD3") (pin "55") (pinfunction "PF6(ADC6/TDO)_55") (pintype "unspecified"))
    )
    (net (code "139") (name "unconnected-(DD3-PF7(ADC7{slash}TDI)-Pad54)") (class "Default")
      (node (ref "DD3") (pin "54") (pinfunction "PF7(ADC7/TDI)_54") (pintype "unspecified"))
    )
    (net (code "140") (name "unconnected-(DD3-TOSC1{slash}PG4-Pad19)") (class "Default")
      (node (ref "DD3") (pin "19") (pinfunction "TOSC1/PG4_19") (pintype "unspecified"))
    )
    (net (code "141") (name "unconnected-(DD3-TOSC2{slash}PG3-Pad18)") (class "Default")
      (node (ref "DD3") (pin "18") (pinfunction "TOSC2/PG3_18") (pintype "unspecified"))
    )
    (net (code "142") (name "unconnected-(DD4-NC-Pad5)") (class "Default")
      (node (ref "DD4") (pin "5") (pinfunction "NC_5") (pintype "unspecified"))
    )
    (net (code "143") (name "unconnected-(KEY1-Pad3)") (class "Default")
      (node (ref "KEY1") (pin "3") (pinfunction "3_3") (pintype "unspecified"))
    )
    (net (code "144") (name "unconnected-(KEY2-Pad3)") (class "Default")
      (node (ref "KEY2") (pin "3") (pinfunction "3_3") (pintype "unspecified"))
    )
    (net (code "145") (name "unconnected-(KEY3-Pad1)") (class "Default")
      (node (ref "KEY3") (pin "1") (pinfunction "1_1") (pintype "unspecified"))
    )
    (net (code "146") (name "unconnected-(KEY4-Pad4)") (class "Default")
      (node (ref "KEY4") (pin "4") (pinfunction "4_4") (pintype "unspecified"))
    )
    (net (code "147") (name "unconnected-(U1-A3-Pad4)") (class "Default")
      (node (ref "U1") (pin "4") (pinfunction "A3_4") (pintype "unspecified"))
    )
    (net (code "148") (name "unconnected-(U1-A4-Pad5)") (class "Default")
      (node (ref "U1") (pin "5") (pinfunction "A4_5") (pintype "unspecified"))
    )
    (net (code "149") (name "unconnected-(U1-A5-Pad6)") (class "Default")
      (node (ref "U1") (pin "6") (pinfunction "A5_6") (pintype "unspecified"))
    )
    (net (code "150") (name "unconnected-(U1-A6-Pad7)") (class "Default")
      (node (ref "U1") (pin "7") (pinfunction "A6_7") (pintype "unspecified"))
    )
    (net (code "151") (name "unconnected-(U1-A7-Pad8)") (class "Default")
      (node (ref "U1") (pin "8") (pinfunction "A7_8") (pintype "unspecified"))
    )
    (net (code "152") (name "unconnected-(U1-A8-Pad9)") (class "Default")
      (node (ref "U1") (pin "9") (pinfunction "A8_9") (pintype "unspecified"))
    )
    (net (code "153") (name "unconnected-(U1-B3-Pad17)") (class "Default")
      (node (ref "U1") (pin "17") (pinfunction "B3_17") (pintype "unspecified"))
    )
    (net (code "154") (name "unconnected-(U1-B4-Pad16)") (class "Default")
      (node (ref "U1") (pin "16") (pinfunction "B4_16") (pintype "unspecified"))
    )
    (net (code "155") (name "unconnected-(U1-B5-Pad15)") (class "Default")
      (node (ref "U1") (pin "15") (pinfunction "B5_15") (pintype "unspecified"))
    )
    (net (code "156") (name "unconnected-(U1-B6-Pad14)") (class "Default")
      (node (ref "U1") (pin "14") (pinfunction "B6_14") (pintype "unspecified"))
    )
    (net (code "157") (name "unconnected-(U1-B7-Pad13)") (class "Default")
      (node (ref "U1") (pin "13") (pinfunction "B7_13") (pintype "unspecified"))
    )
    (net (code "158") (name "unconnected-(U1-B8-Pad12)") (class "Default")
      (node (ref "U1") (pin "12") (pinfunction "B8_12") (pintype "unspecified"))
    )
    (net (code "159") (name "unconnected-(X2-ID-Pad4)") (class "Default")
      (node (ref "X2") (pin "4") (pinfunction "ID_4") (pintype "unspecified"))
    )
    (net (code "160") (name "unconnected-(X6-CHS_GND-Pad8)") (class "Default")
      (node (ref "X6") (pin "8") (pinfunction "CHS_GND_8") (pintype "unspecified"))
    )
    (net (code "161") (name "unconnected-(X6-NC-Pad7)") (class "Default")
      (node (ref "X6") (pin "7") (pinfunction "NC_7") (pintype "unspecified"))
    )
  )
)
